# Microcontroller.net
KiCad netlist of a schematic drawn in Altium Designer
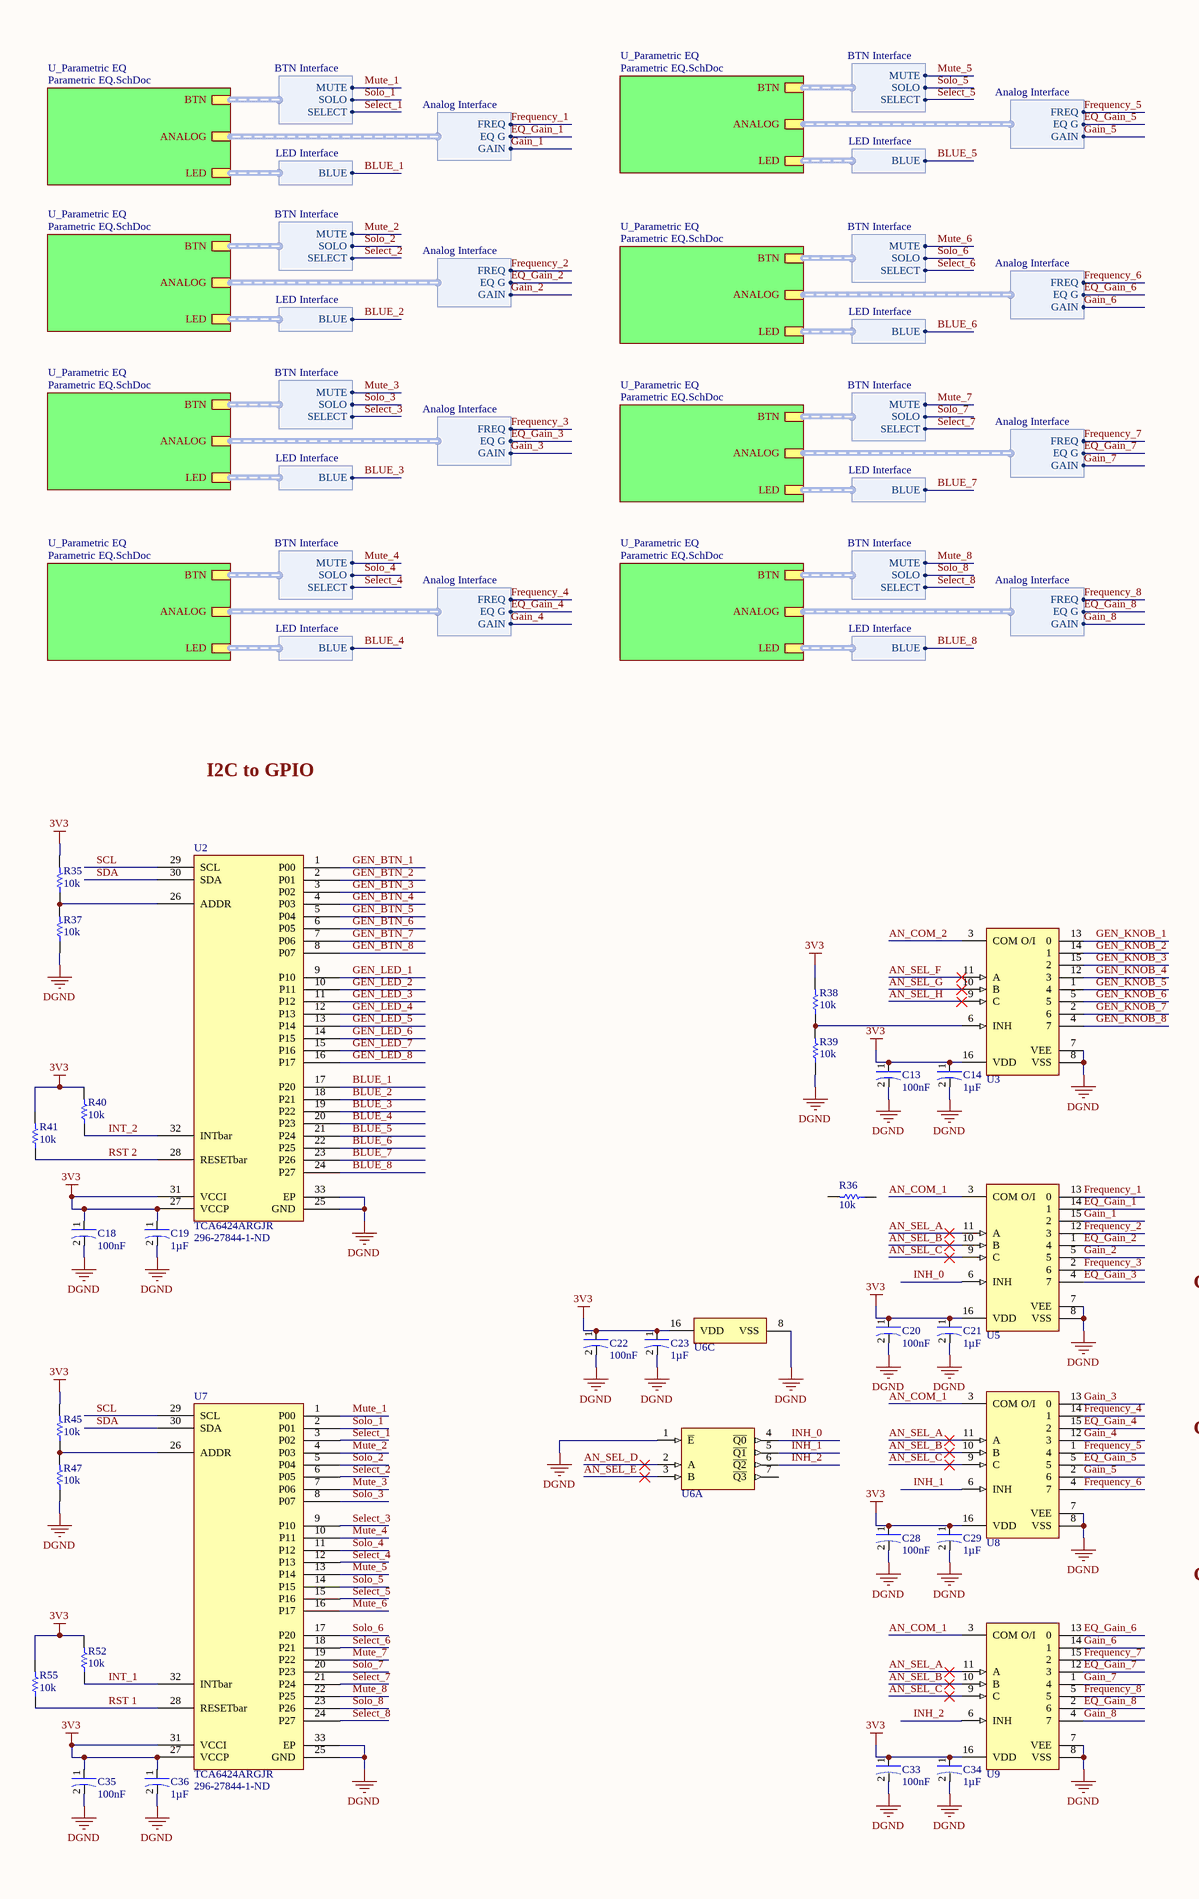
[diagram p0: Microcontroller.SchDoc, left]
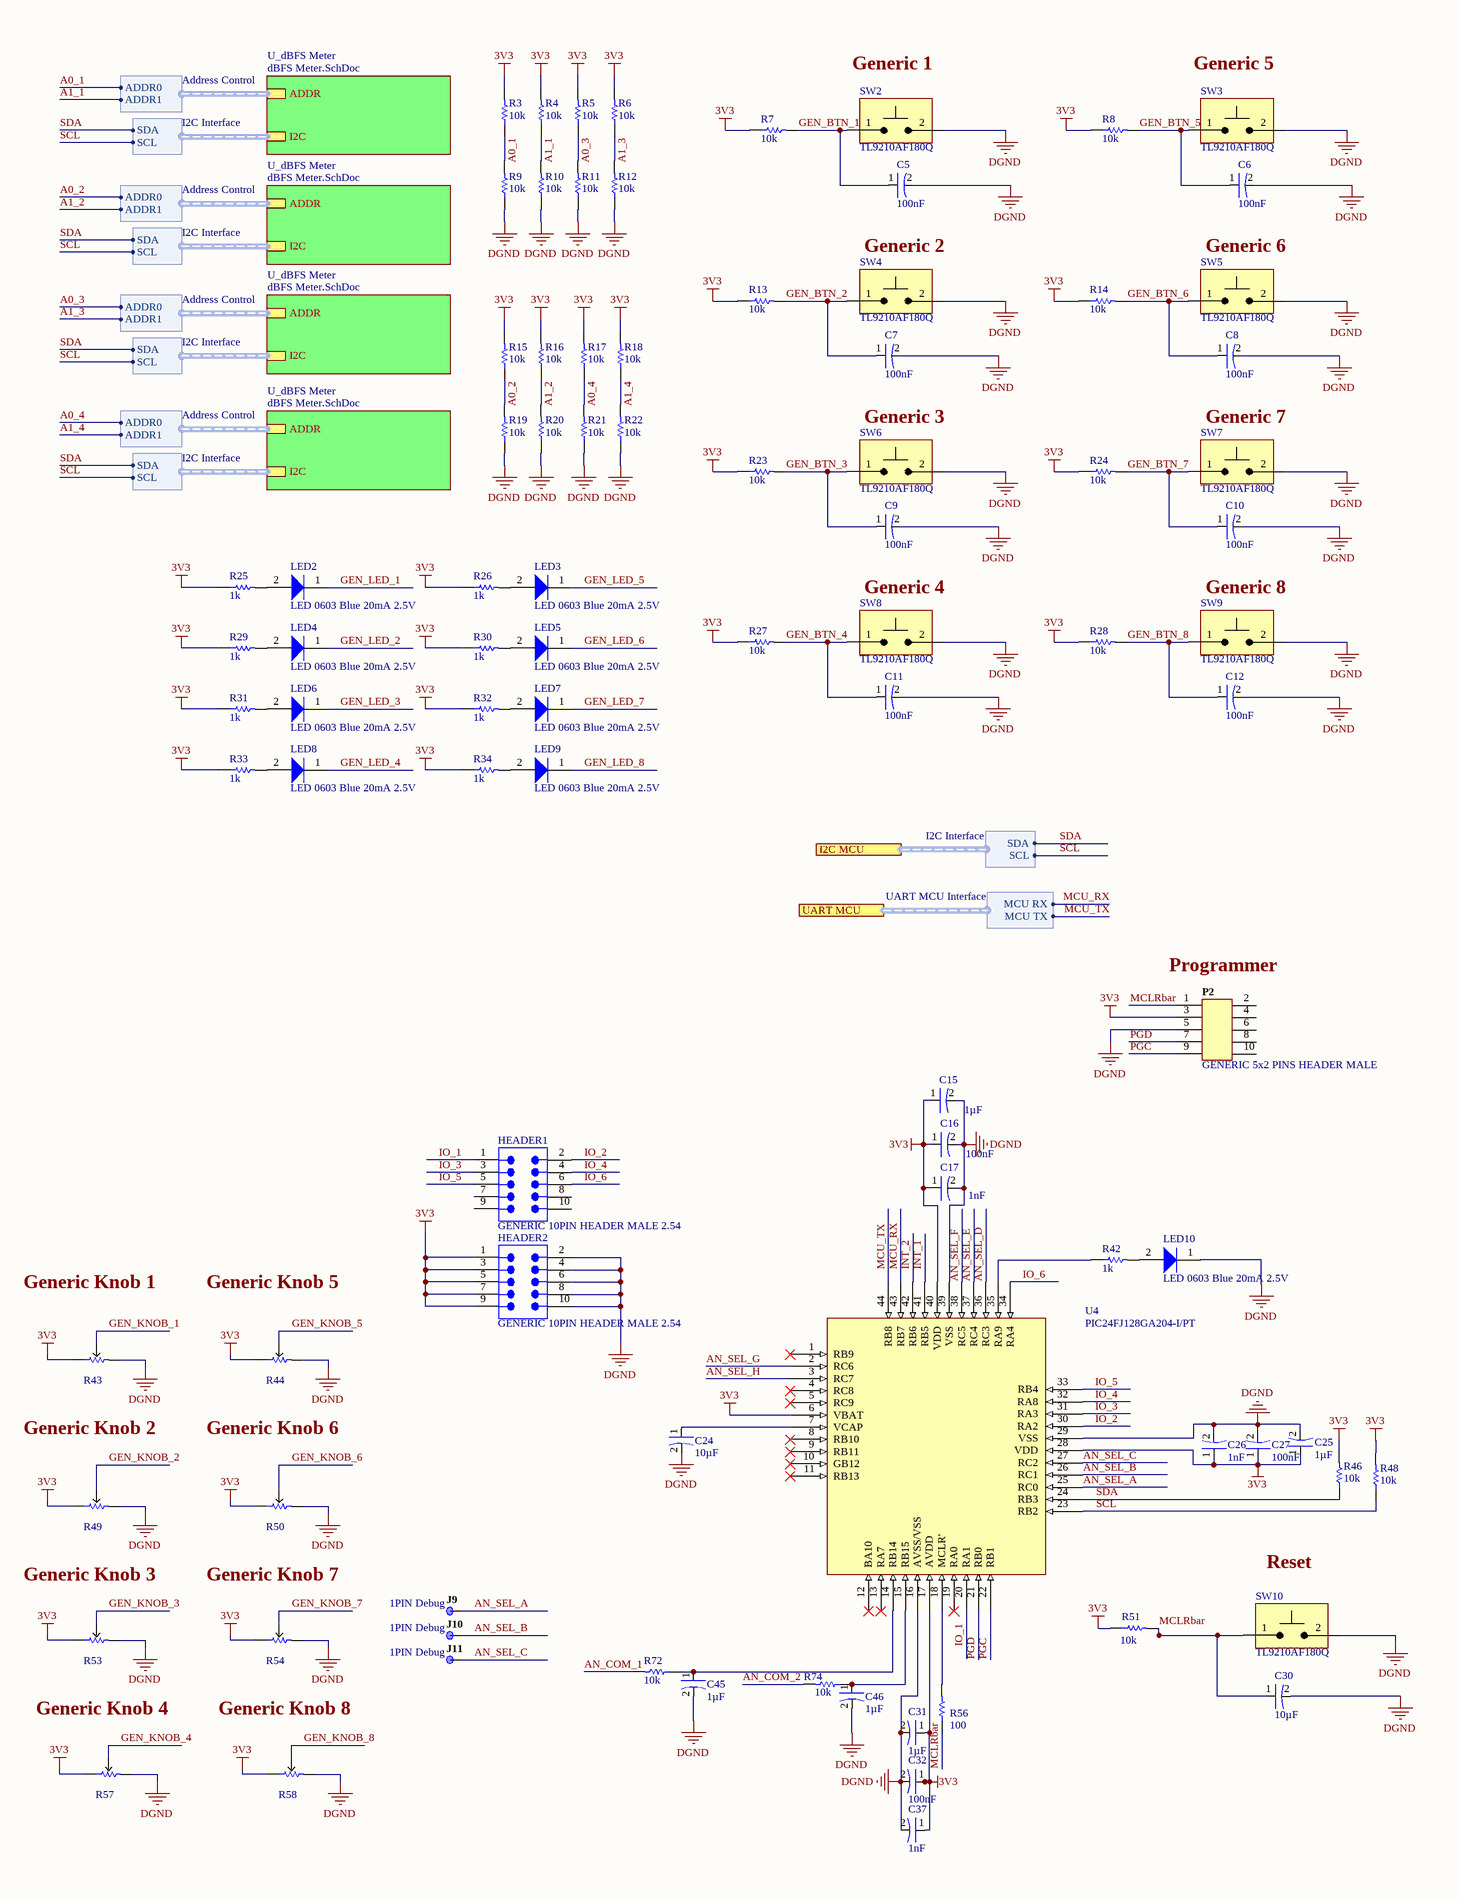
[diagram p1: Microcontroller.SchDoc, right]

(export (version "E")
  (design (tool "Eeschema 10.0.6"))
  (components
    (comp (ref "C5")
      (value "100nF")
      (footprint "0402-M")
      (description "CAP-0.1uF-CER-0402-16V-X5R-10%")
      (fields
        (field (name "MANUFACTURER") "Generic")
        (field (name "Comment") "CAP 0.1uF CER 0402 16V X5R 10%")
      )
      (libsource (lib "University of Malta - MEMENTO") (part "Symbol"))
    )
    (comp (ref "C6")
      (value "100nF")
      (footprint "0402-M")
      (description "CAP-0.1uF-CER-0402-16V-X5R-10%")
      (fields
        (field (name "MANUFACTURER") "Generic")
        (field (name "Comment") "CAP 0.1uF CER 0402 16V X5R 10%")
      )
      (libsource (lib "University of Malta - MEMENTO") (part "Symbol"))
    )
    (comp (ref "C7")
      (value "100nF")
      (footprint "0402-M")
      (description "CAP-0.1uF-CER-0402-16V-X5R-10%")
      (fields
        (field (name "MANUFACTURER") "Generic")
        (field (name "Comment") "CAP 0.1uF CER 0402 16V X5R 10%")
      )
      (libsource (lib "University of Malta - MEMENTO") (part "Symbol"))
    )
    (comp (ref "C8")
      (value "100nF")
      (footprint "0402-M")
      (description "CAP-0.1uF-CER-0402-16V-X5R-10%")
      (fields
        (field (name "MANUFACTURER") "Generic")
        (field (name "Comment") "CAP 0.1uF CER 0402 16V X5R 10%")
      )
      (libsource (lib "University of Malta - MEMENTO") (part "Symbol"))
    )
    (comp (ref "C9")
      (value "100nF")
      (footprint "0402-M")
      (description "CAP-0.1uF-CER-0402-16V-X5R-10%")
      (fields
        (field (name "MANUFACTURER") "Generic")
        (field (name "Comment") "CAP 0.1uF CER 0402 16V X5R 10%")
      )
      (libsource (lib "University of Malta - MEMENTO") (part "Symbol"))
    )
    (comp (ref "C10")
      (value "100nF")
      (footprint "0402-M")
      (description "CAP-0.1uF-CER-0402-16V-X5R-10%")
      (fields
        (field (name "MANUFACTURER") "Generic")
        (field (name "Comment") "CAP 0.1uF CER 0402 16V X5R 10%")
      )
      (libsource (lib "University of Malta - MEMENTO") (part "Symbol"))
    )
    (comp (ref "C11")
      (value "100nF")
      (footprint "0402-M")
      (description "CAP-0.1uF-CER-0402-16V-X5R-10%")
      (fields
        (field (name "MANUFACTURER") "Generic")
        (field (name "Comment") "CAP 0.1uF CER 0402 16V X5R 10%")
      )
      (libsource (lib "University of Malta - MEMENTO") (part "Symbol"))
    )
    (comp (ref "C12")
      (value "100nF")
      (footprint "0402-M")
      (description "CAP-0.1uF-CER-0402-16V-X5R-10%")
      (fields
        (field (name "MANUFACTURER") "Generic")
        (field (name "Comment") "CAP 0.1uF CER 0402 16V X5R 10%")
      )
      (libsource (lib "University of Malta - MEMENTO") (part "Symbol"))
    )
    (comp (ref "C13")
      (value "100nF")
      (footprint "0805-M")
      (description "CAP-0.1uF-CER-0805-50V- X7R-5%")
      (fields
        (field (name "MANUFACTURER") "Generic")
        (field (name "Comment") "CAP 0.1uF CER 0805 50V  X7R 5%")
      )
      (libsource (lib "University of Malta - MEMENTO") (part "Symbol"))
    )
    (comp (ref "C14")
      (value "1µF")
      (footprint "0805-M")
      (description "CAP 1uF CER 0805 25V C0G 10%")
      (fields (field (name "MANUFACTURER") "Generic"))
      (libsource (lib "University of Malta - MEMENTO") (part "Symbol"))
    )
    (comp (ref "C15")
      (value "1µF")
      (footprint "0805-M")
      (description "CAP 1uF CER 0805 25V C0G 10%")
      (fields (field (name "MANUFACTURER") "Generic"))
      (libsource (lib "University of Malta - MEMENTO") (part "Symbol"))
    )
    (comp (ref "C16")
      (value "100nF")
      (footprint "0805-M")
      (description "CAP-0.1uF-CER-0805-50V- X7R-5%")
      (fields
        (field (name "MANUFACTURER") "Generic")
        (field (name "Comment") "CAP 0.1uF CER 0805 50V  X7R 5%")
      )
      (libsource (lib "University of Malta - MEMENTO") (part "Symbol"))
    )
    (comp (ref "C17")
      (value "1nF")
      (footprint "0805-M")
      (description "CAP 1nF CER 0805 25V X7R 5%")
      (fields (field (name "MANUFACTURER") "Generic"))
      (libsource (lib "University of Malta - MEMENTO") (part "Symbol"))
    )
    (comp (ref "C18")
      (value "100nF")
      (footprint "0805-M")
      (description "CAP-0.1uF-CER-0805-50V- X7R-5%")
      (fields
        (field (name "MANUFACTURER") "Generic")
        (field (name "Comment") "CAP 0.1uF CER 0805 50V  X7R 5%")
      )
      (libsource (lib "University of Malta - MEMENTO") (part "Symbol"))
    )
    (comp (ref "C19")
      (value "1µF")
      (footprint "0805-M")
      (description "CAP 1uF CER 0805 25V C0G 10%")
      (fields (field (name "MANUFACTURER") "Generic"))
      (libsource (lib "University of Malta - MEMENTO") (part "Symbol"))
    )
    (comp (ref "C20")
      (value "100nF")
      (footprint "0805-M")
      (description "CAP-0.1uF-CER-0805-50V- X7R-5%")
      (fields
        (field (name "MANUFACTURER") "Generic")
        (field (name "Comment") "CAP 0.1uF CER 0805 50V  X7R 5%")
      )
      (libsource (lib "University of Malta - MEMENTO") (part "Symbol"))
    )
    (comp (ref "C21")
      (value "1µF")
      (footprint "0805-M")
      (description "CAP 1uF CER 0805 25V C0G 10%")
      (fields (field (name "MANUFACTURER") "Generic"))
      (libsource (lib "University of Malta - MEMENTO") (part "Symbol"))
    )
    (comp (ref "C22")
      (value "100nF")
      (footprint "0805-M")
      (description "CAP-0.1uF-CER-0805-50V- X7R-5%")
      (fields
        (field (name "MANUFACTURER") "Generic")
        (field (name "Comment") "CAP 0.1uF CER 0805 50V  X7R 5%")
      )
      (libsource (lib "University of Malta - MEMENTO") (part "Symbol"))
    )
    (comp (ref "C23")
      (value "1µF")
      (footprint "0805-M")
      (description "CAP 1uF CER 0805 25V C0G 10%")
      (fields (field (name "MANUFACTURER") "Generic"))
      (libsource (lib "University of Malta - MEMENTO") (part "Symbol"))
    )
    (comp (ref "C24")
      (value "10µF")
      (footprint "0805-M")
      (description "CAP-10uF-CER-0805-25V-X5R-10%")
      (fields
        (field (name "MANUFACTURER") "Generic")
        (field (name "Comment") "CAP 10uF CER 0805 25V X5R 10%")
      )
      (libsource (lib "University of Malta - MEMENTO") (part "Symbol"))
    )
    (comp (ref "C25")
      (value "1µF")
      (footprint "0805-M")
      (description "CAP 1uF CER 0805 25V C0G 10%")
      (fields (field (name "MANUFACTURER") "Generic"))
      (libsource (lib "University of Malta - MEMENTO") (part "Symbol"))
    )
    (comp (ref "C26")
      (value "1nF")
      (footprint "0805-M")
      (description "CAP 1nF CER 0805 25V X7R 5%")
      (fields (field (name "MANUFACTURER") "Generic"))
      (libsource (lib "University of Malta - MEMENTO") (part "Symbol"))
    )
    (comp (ref "C27")
      (value "100nF")
      (footprint "0805-M")
      (description "CAP-0.1uF-CER-0805-50V- X7R-5%")
      (fields
        (field (name "MANUFACTURER") "Generic")
        (field (name "Comment") "CAP 0.1uF CER 0805 50V  X7R 5%")
      )
      (libsource (lib "University of Malta - MEMENTO") (part "Symbol"))
    )
    (comp (ref "C28")
      (value "100nF")
      (footprint "0805-M")
      (description "CAP-0.1uF-CER-0805-50V- X7R-5%")
      (fields
        (field (name "MANUFACTURER") "Generic")
        (field (name "Comment") "CAP 0.1uF CER 0805 50V  X7R 5%")
      )
      (libsource (lib "University of Malta - MEMENTO") (part "Symbol"))
    )
    (comp (ref "C29")
      (value "1µF")
      (footprint "0805-M")
      (description "CAP 1uF CER 0805 25V C0G 10%")
      (fields (field (name "MANUFACTURER") "Generic"))
      (libsource (lib "University of Malta - MEMENTO") (part "Symbol"))
    )
    (comp (ref "C30")
      (value "10µF")
      (footprint "0402-M")
      (description "CAP-10uF-CER-0402-6.3V-X5R-20%")
      (fields
        (field (name "MANUFACTURER") "Generic")
        (field (name "Comment") "CAP 10uF CER 0402 6.3V X5R 20%")
      )
      (libsource (lib "University of Malta - MEMENTO") (part "Symbol"))
    )
    (comp (ref "C31")
      (value "1µF")
      (footprint "0805-M")
      (description "CAP 1uF CER 0805 25V C0G 10%")
      (fields (field (name "MANUFACTURER") "Generic"))
      (libsource (lib "University of Malta - MEMENTO") (part "Symbol"))
    )
    (comp (ref "C32")
      (value "100nF")
      (footprint "0805-M")
      (description "CAP-0.1uF-CER-0805-50V- X7R-5%")
      (fields
        (field (name "MANUFACTURER") "Generic")
        (field (name "Comment") "CAP 0.1uF CER 0805 50V  X7R 5%")
      )
      (libsource (lib "University of Malta - MEMENTO") (part "Symbol"))
    )
    (comp (ref "C33")
      (value "100nF")
      (footprint "0805-M")
      (description "CAP-0.1uF-CER-0805-50V- X7R-5%")
      (fields
        (field (name "MANUFACTURER") "Generic")
        (field (name "Comment") "CAP 0.1uF CER 0805 50V  X7R 5%")
      )
      (libsource (lib "University of Malta - MEMENTO") (part "Symbol"))
    )
    (comp (ref "C34")
      (value "1µF")
      (footprint "0805-M")
      (description "CAP 1uF CER 0805 25V C0G 10%")
      (fields (field (name "MANUFACTURER") "Generic"))
      (libsource (lib "University of Malta - MEMENTO") (part "Symbol"))
    )
    (comp (ref "C35")
      (value "100nF")
      (footprint "0805-M")
      (description "CAP-0.1uF-CER-0805-50V- X7R-5%")
      (fields
        (field (name "MANUFACTURER") "Generic")
        (field (name "Comment") "CAP 0.1uF CER 0805 50V  X7R 5%")
      )
      (libsource (lib "University of Malta - MEMENTO") (part "Symbol"))
    )
    (comp (ref "C36")
      (value "1µF")
      (footprint "0805-M")
      (description "CAP 1uF CER 0805 25V C0G 10%")
      (fields (field (name "MANUFACTURER") "Generic"))
      (libsource (lib "University of Malta - MEMENTO") (part "Symbol"))
    )
    (comp (ref "C37")
      (value "1nF")
      (footprint "0805-M")
      (description "CAP 1nF CER 0805 25V X7R 5%")
      (fields (field (name "MANUFACTURER") "Generic"))
      (libsource (lib "University of Malta - MEMENTO") (part "Symbol"))
    )
    (comp (ref "C45")
      (value "1µF")
      (footprint "0402-M")
      (description "CAP-1uF-CER-0402-6.3V-X5R-10%")
      (fields
        (field (name "MANUFACTURER") "Generic")
        (field (name "Comment") "CAP 1uF CER 0402 6.3V X5R 10%")
      )
      (libsource (lib "University of Malta - MEMENTO") (part "Symbol"))
    )
    (comp (ref "C46")
      (value "1µF")
      (footprint "0402-M")
      (description "CAP-1uF-CER-0402-6.3V-X5R-10%")
      (fields
        (field (name "MANUFACTURER") "Generic")
        (field (name "Comment") "CAP 1uF CER 0402 6.3V X5R 10%")
      )
      (libsource (lib "University of Malta - MEMENTO") (part "Symbol"))
    )
    (comp (ref "HEADER1")
      (value "GENERIC 10PIN HEADER MALE 2.54")
      (footprint "GENERIC 10Pin Header Male 2.54mm")
      (description "CONN MAL TH 10 0Deg HEADER 2.54mm")
      (fields
        (field (name "MANUFACTURER") "Generic")
        (field (name "DESIGN ITEM ID") "GENERIC 10PIN HEADER MALE 2.54")
      )
      (libsource (lib "University of Malta - MEMENTO") (part "GENERIC 10PIN HEADER MALE 2.54"))
    )
    (comp (ref "HEADER2")
      (value "GENERIC 10PIN HEADER MALE 2.54")
      (footprint "GENERIC 10Pin Header Male 2.54mm")
      (description "CONN MAL TH 10 0Deg HEADER 2.54mm")
      (fields
        (field (name "MANUFACTURER") "Generic")
        (field (name "DESIGN ITEM ID") "GENERIC 10PIN HEADER MALE 2.54")
      )
      (libsource (lib "University of Malta - MEMENTO") (part "GENERIC 10PIN HEADER MALE 2.54"))
    )
    (comp (ref "J9")
      (value "1PIN Debug")
      (footprint "1 Pin Debug Port 0.9mm")
      (description "CONN MAL TH 1 0Deg HEADER")
      (fields (field (name "DESIGN ITEM ID") "1PIN Debug"))
      (libsource (lib "University of Malta - MEMENTO") (part "1PIN Debug"))
    )
    (comp (ref "J10")
      (value "1PIN Debug")
      (footprint "1 Pin Debug Port 0.9mm")
      (description "CONN MAL TH 1 0Deg HEADER")
      (fields (field (name "DESIGN ITEM ID") "1PIN Debug"))
      (libsource (lib "University of Malta - MEMENTO") (part "1PIN Debug"))
    )
    (comp (ref "J11")
      (value "1PIN Debug")
      (footprint "1 Pin Debug Port 0.9mm")
      (description "CONN MAL TH 1 0Deg HEADER")
      (fields (field (name "DESIGN ITEM ID") "1PIN Debug"))
      (libsource (lib "University of Malta - MEMENTO") (part "1PIN Debug"))
    )
    (comp (ref "LED2")
      (value "LED 0603 Blue 20mA 2.5V")
      (footprint "VAOL-S6SB4")
      (description "LED-0603-Blue-20mA-2.5V-STOCK")
      (fields
        (field (name "DESIGN ITEM ID") "LED 0603 Blue 20mA 2.5V")
        (field (name "MANUFACTURER") "Generic")
      )
      (libsource (lib "") (part "Symbol_2"))
    )
    (comp (ref "LED3")
      (value "LED 0603 Blue 20mA 2.5V")
      (footprint "VAOL-S6SB4")
      (description "LED-0603-Blue-20mA-2.5V-STOCK")
      (fields
        (field (name "DESIGN ITEM ID") "LED 0603 Blue 20mA 2.5V")
        (field (name "MANUFACTURER") "Generic")
      )
      (libsource (lib "") (part "Symbol_2"))
    )
    (comp (ref "LED4")
      (value "LED 0603 Blue 20mA 2.5V")
      (footprint "VAOL-S6SB4")
      (description "LED-0603-Blue-20mA-2.5V-STOCK")
      (fields
        (field (name "DESIGN ITEM ID") "LED 0603 Blue 20mA 2.5V")
        (field (name "MANUFACTURER") "Generic")
      )
      (libsource (lib "") (part "Symbol_2"))
    )
    (comp (ref "LED5")
      (value "LED 0603 Blue 20mA 2.5V")
      (footprint "VAOL-S6SB4")
      (description "LED-0603-Blue-20mA-2.5V-STOCK")
      (fields
        (field (name "DESIGN ITEM ID") "LED 0603 Blue 20mA 2.5V")
        (field (name "MANUFACTURER") "Generic")
      )
      (libsource (lib "") (part "Symbol_2"))
    )
    (comp (ref "LED6")
      (value "LED 0603 Blue 20mA 2.5V")
      (footprint "VAOL-S6SB4")
      (description "LED-0603-Blue-20mA-2.5V-STOCK")
      (fields
        (field (name "DESIGN ITEM ID") "LED 0603 Blue 20mA 2.5V")
        (field (name "MANUFACTURER") "Generic")
      )
      (libsource (lib "") (part "Symbol_2"))
    )
    (comp (ref "LED7")
      (value "LED 0603 Blue 20mA 2.5V")
      (footprint "VAOL-S6SB4")
      (description "LED-0603-Blue-20mA-2.5V-STOCK")
      (fields
        (field (name "DESIGN ITEM ID") "LED 0603 Blue 20mA 2.5V")
        (field (name "MANUFACTURER") "Generic")
      )
      (libsource (lib "") (part "Symbol_2"))
    )
    (comp (ref "LED8")
      (value "LED 0603 Blue 20mA 2.5V")
      (footprint "VAOL-S6SB4")
      (description "LED-0603-Blue-20mA-2.5V-STOCK")
      (fields
        (field (name "DESIGN ITEM ID") "LED 0603 Blue 20mA 2.5V")
        (field (name "MANUFACTURER") "Generic")
      )
      (libsource (lib "") (part "Symbol_2"))
    )
    (comp (ref "LED9")
      (value "LED 0603 Blue 20mA 2.5V")
      (footprint "VAOL-S6SB4")
      (description "LED-0603-Blue-20mA-2.5V-STOCK")
      (fields
        (field (name "DESIGN ITEM ID") "LED 0603 Blue 20mA 2.5V")
        (field (name "MANUFACTURER") "Generic")
      )
      (libsource (lib "") (part "Symbol_2"))
    )
    (comp (ref "LED10")
      (value "LED 0603 Blue 20mA 2.5V")
      (footprint "VAOL-S6SB4")
      (description "LED-0603-Blue-20mA-2.5V-STOCK")
      (fields
        (field (name "DESIGN ITEM ID") "LED 0603 Blue 20mA 2.5V")
        (field (name "MANUFACTURER") "Generic")
      )
      (libsource (lib "") (part "Symbol_2"))
    )
    (comp (ref "P2")
      (value "GENERIC 5x2 PINS HEADER MALE")
      (footprint "GENERIC 5PIN 2ROW HEADER 0")
      (description "CONN MAL TH 5x2 0Deg HEADER")
      (fields
        (field (name "DESIGN ITEM ID") "GENERIC 5x2 PINS HEADER MALE")
        (field (name "MANUFACTURER") "Generic")
      )
      (libsource (lib "University of Malta - MEMENTO") (part "GENERIC 5x2 PINS HEADER MALE"))
    )
    (comp (ref "R3")
      (value "10k")
      (footprint "0402-M")
      (description "RES-10k-0402-63mW-5%")
      (fields (field (name "MANUFACTURER") "Generic") (field (name "Comment") "RES 10k 0402 63mW 5%"))
      (libsource (lib "") (part "Symbol_1"))
    )
    (comp (ref "R4")
      (value "10k")
      (footprint "0402-M")
      (description "RES-10k-0402-63mW-5%")
      (fields (field (name "MANUFACTURER") "Generic") (field (name "Comment") "RES 10k 0402 63mW 5%"))
      (libsource (lib "") (part "Symbol_1"))
    )
    (comp (ref "R5")
      (value "10k")
      (footprint "0402-M")
      (description "RES-10k-0402-63mW-5%")
      (fields (field (name "MANUFACTURER") "Generic") (field (name "Comment") "RES 10k 0402 63mW 5%"))
      (libsource (lib "") (part "Symbol_1"))
    )
    (comp (ref "R6")
      (value "10k")
      (footprint "0402-M")
      (description "RES-10k-0402-63mW-5%")
      (fields (field (name "MANUFACTURER") "Generic") (field (name "Comment") "RES 10k 0402 63mW 5%"))
      (libsource (lib "") (part "Symbol_1"))
    )
    (comp (ref "R7")
      (value "10k")
      (footprint "0402-M")
      (description "RES-10k-0402-63mW-5%")
      (fields (field (name "MANUFACTURER") "Generic") (field (name "Comment") "RES 10k 0402 63mW 5%"))
      (libsource (lib "") (part "Symbol_1"))
    )
    (comp (ref "R8")
      (value "10k")
      (footprint "0402-M")
      (description "RES-10k-0402-63mW-5%")
      (fields (field (name "MANUFACTURER") "Generic") (field (name "Comment") "RES 10k 0402 63mW 5%"))
      (libsource (lib "") (part "Symbol_1"))
    )
    (comp (ref "R9")
      (value "10k")
      (footprint "0402-M")
      (description "RES-10k-0402-63mW-5%")
      (fields (field (name "MANUFACTURER") "Generic") (field (name "Comment") "RES 10k 0402 63mW 5%"))
      (libsource (lib "") (part "Symbol_1"))
    )
    (comp (ref "R10")
      (value "10k")
      (footprint "0402-M")
      (description "RES-10k-0402-63mW-5%")
      (fields (field (name "MANUFACTURER") "Generic") (field (name "Comment") "RES 10k 0402 63mW 5%"))
      (libsource (lib "") (part "Symbol_1"))
    )
    (comp (ref "R11")
      (value "10k")
      (footprint "0402-M")
      (description "RES-10k-0402-63mW-5%")
      (fields (field (name "MANUFACTURER") "Generic") (field (name "Comment") "RES 10k 0402 63mW 5%"))
      (libsource (lib "") (part "Symbol_1"))
    )
    (comp (ref "R12")
      (value "10k")
      (footprint "0402-M")
      (description "RES-10k-0402-63mW-5%")
      (fields (field (name "MANUFACTURER") "Generic") (field (name "Comment") "RES 10k 0402 63mW 5%"))
      (libsource (lib "") (part "Symbol_1"))
    )
    (comp (ref "R13")
      (value "10k")
      (footprint "0402-M")
      (description "RES-10k-0402-63mW-5%")
      (fields (field (name "MANUFACTURER") "Generic") (field (name "Comment") "RES 10k 0402 63mW 5%"))
      (libsource (lib "") (part "Symbol_1"))
    )
    (comp (ref "R14")
      (value "10k")
      (footprint "0402-M")
      (description "RES-10k-0402-63mW-5%")
      (fields (field (name "MANUFACTURER") "Generic") (field (name "Comment") "RES 10k 0402 63mW 5%"))
      (libsource (lib "") (part "Symbol_1"))
    )
    (comp (ref "R15")
      (value "10k")
      (footprint "0402-M")
      (description "RES-10k-0402-63mW-5%")
      (fields (field (name "MANUFACTURER") "Generic") (field (name "Comment") "RES 10k 0402 63mW 5%"))
      (libsource (lib "") (part "Symbol_1"))
    )
    (comp (ref "R16")
      (value "10k")
      (footprint "0402-M")
      (description "RES-10k-0402-63mW-5%")
      (fields (field (name "MANUFACTURER") "Generic") (field (name "Comment") "RES 10k 0402 63mW 5%"))
      (libsource (lib "") (part "Symbol_1"))
    )
    (comp (ref "R17")
      (value "10k")
      (footprint "0402-M")
      (description "RES-10k-0402-63mW-5%")
      (fields (field (name "MANUFACTURER") "Generic") (field (name "Comment") "RES 10k 0402 63mW 5%"))
      (libsource (lib "") (part "Symbol_1"))
    )
    (comp (ref "R18")
      (value "10k")
      (footprint "0402-M")
      (description "RES-10k-0402-63mW-5%")
      (fields (field (name "MANUFACTURER") "Generic") (field (name "Comment") "RES 10k 0402 63mW 5%"))
      (libsource (lib "") (part "Symbol_1"))
    )
    (comp (ref "R19")
      (value "10k")
      (footprint "0402-M")
      (description "RES-10k-0402-63mW-5%")
      (fields (field (name "MANUFACTURER") "Generic") (field (name "Comment") "RES 10k 0402 63mW 5%"))
      (libsource (lib "") (part "Symbol_1"))
    )
    (comp (ref "R20")
      (value "10k")
      (footprint "0402-M")
      (description "RES-10k-0402-63mW-5%")
      (fields (field (name "MANUFACTURER") "Generic") (field (name "Comment") "RES 10k 0402 63mW 5%"))
      (libsource (lib "") (part "Symbol_1"))
    )
    (comp (ref "R21")
      (value "10k")
      (footprint "0402-M")
      (description "RES-10k-0402-63mW-5%")
      (fields (field (name "MANUFACTURER") "Generic") (field (name "Comment") "RES 10k 0402 63mW 5%"))
      (libsource (lib "") (part "Symbol_1"))
    )
    (comp (ref "R22")
      (value "10k")
      (footprint "0402-M")
      (description "RES-10k-0402-63mW-5%")
      (fields (field (name "MANUFACTURER") "Generic") (field (name "Comment") "RES 10k 0402 63mW 5%"))
      (libsource (lib "") (part "Symbol_1"))
    )
    (comp (ref "R23")
      (value "10k")
      (footprint "0402-M")
      (description "RES-10k-0402-63mW-5%")
      (fields (field (name "MANUFACTURER") "Generic") (field (name "Comment") "RES 10k 0402 63mW 5%"))
      (libsource (lib "") (part "Symbol_1"))
    )
    (comp (ref "R24")
      (value "10k")
      (footprint "0402-M")
      (description "RES-10k-0402-63mW-5%")
      (fields (field (name "MANUFACTURER") "Generic") (field (name "Comment") "RES 10k 0402 63mW 5%"))
      (libsource (lib "") (part "Symbol_1"))
    )
    (comp (ref "R25")
      (value "1k")
      (footprint "0402-M")
      (description "RES-1k-0402-63mW-1%")
      (fields (field (name "MANUFACTURER") "Generic") (field (name "Comment") "RES 1k 0402 63mW 1%"))
      (libsource (lib "") (part "Symbol_1"))
    )
    (comp (ref "R26")
      (value "1k")
      (footprint "0402-M")
      (description "RES-1k-0402-63mW-1%")
      (fields (field (name "MANUFACTURER") "Generic") (field (name "Comment") "RES 1k 0402 63mW 1%"))
      (libsource (lib "") (part "Symbol_1"))
    )
    (comp (ref "R27")
      (value "10k")
      (footprint "0402-M")
      (description "RES-10k-0402-63mW-5%")
      (fields (field (name "MANUFACTURER") "Generic") (field (name "Comment") "RES 10k 0402 63mW 5%"))
      (libsource (lib "") (part "Symbol_1"))
    )
    (comp (ref "R28")
      (value "10k")
      (footprint "0402-M")
      (description "RES-10k-0402-63mW-5%")
      (fields (field (name "MANUFACTURER") "Generic") (field (name "Comment") "RES 10k 0402 63mW 5%"))
      (libsource (lib "") (part "Symbol_1"))
    )
    (comp (ref "R29")
      (value "1k")
      (footprint "0402-M")
      (description "RES-1k-0402-63mW-1%")
      (fields (field (name "MANUFACTURER") "Generic") (field (name "Comment") "RES 1k 0402 63mW 1%"))
      (libsource (lib "") (part "Symbol_1"))
    )
    (comp (ref "R30")
      (value "1k")
      (footprint "0402-M")
      (description "RES-1k-0402-63mW-1%")
      (fields (field (name "MANUFACTURER") "Generic") (field (name "Comment") "RES 1k 0402 63mW 1%"))
      (libsource (lib "") (part "Symbol_1"))
    )
    (comp (ref "R31")
      (value "1k")
      (footprint "0402-M")
      (description "RES-1k-0402-63mW-1%")
      (fields (field (name "MANUFACTURER") "Generic") (field (name "Comment") "RES 1k 0402 63mW 1%"))
      (libsource (lib "") (part "Symbol_1"))
    )
    (comp (ref "R32")
      (value "1k")
      (footprint "0402-M")
      (description "RES-1k-0402-63mW-1%")
      (fields (field (name "MANUFACTURER") "Generic") (field (name "Comment") "RES 1k 0402 63mW 1%"))
      (libsource (lib "") (part "Symbol_1"))
    )
    (comp (ref "R33")
      (value "1k")
      (footprint "0402-M")
      (description "RES-1k-0402-63mW-1%")
      (fields (field (name "MANUFACTURER") "Generic") (field (name "Comment") "RES 1k 0402 63mW 1%"))
      (libsource (lib "") (part "Symbol_1"))
    )
    (comp (ref "R34")
      (value "1k")
      (footprint "0402-M")
      (description "RES-1k-0402-63mW-1%")
      (fields (field (name "MANUFACTURER") "Generic") (field (name "Comment") "RES 1k 0402 63mW 1%"))
      (libsource (lib "") (part "Symbol_1"))
    )
    (comp (ref "R35")
      (value "10k")
      (footprint "0805-M")
      (description "RES-10k-0805-125mW-1%")
      (fields (field (name "MANUFACTURER") "Generic") (field (name "Comment") "RES 10k 0805 125mW 1%"))
      (libsource (lib "") (part "Symbol_1"))
    )
    (comp (ref "R36")
      (value "10k")
      (footprint "0402-M")
      (description "RES-10k-0402-63mW-5%")
      (fields (field (name "MANUFACTURER") "Generic") (field (name "Comment") "RES 10k 0402 63mW 5%"))
      (libsource (lib "") (part "Symbol_1"))
    )
    (comp (ref "R37")
      (value "10k")
      (footprint "0805-M")
      (description "RES-10k-0805-125mW-1%")
      (fields (field (name "MANUFACTURER") "Generic") (field (name "Comment") "RES 10k 0805 125mW 1%"))
      (libsource (lib "") (part "Symbol_1"))
    )
    (comp (ref "R38")
      (value "10k")
      (footprint "0805-M")
      (description "RES-10k-0805-125mW-1%")
      (fields (field (name "MANUFACTURER") "Generic") (field (name "Comment") "RES 10k 0805 125mW 1%"))
      (libsource (lib "") (part "Symbol_1"))
    )
    (comp (ref "R39")
      (value "10k")
      (footprint "0805-M")
      (description "RES-10k-0805-125mW-1%")
      (fields (field (name "MANUFACTURER") "Generic") (field (name "Comment") "RES 10k 0805 125mW 1%"))
      (libsource (lib "") (part "Symbol_1"))
    )
    (comp (ref "R40")
      (value "10k")
      (footprint "0805-M")
      (description "RES-10k-0805-125mW-1%")
      (fields (field (name "MANUFACTURER") "Generic") (field (name "Comment") "RES 10k 0805 125mW 1%"))
      (libsource (lib "") (part "Symbol_1"))
    )
    (comp (ref "R41")
      (value "10k")
      (footprint "0805-M")
      (description "RES-10k-0805-125mW-1%")
      (fields (field (name "MANUFACTURER") "Generic") (field (name "Comment") "RES 10k 0805 125mW 1%"))
      (libsource (lib "") (part "Symbol_1"))
    )
    (comp (ref "R42")
      (value "1k")
      (footprint "0402-M")
      (description "RES-1k-0402-63mW-1%")
      (fields (field (name "MANUFACTURER") "Generic") (field (name "Comment") "RES 1k 0402 63mW 1%"))
      (libsource (lib "") (part "Symbol_1"))
    )
    (comp (ref "R43")
      (value "P120PK-Y25BR10K")
      (footprint "P120PK-Y25BR10K-Footprint-1")
      (description "Potentiometers 12mm 10K ohm")
      (fields (field (name "TOLERANCE") "20%"))
      (libsource (lib "University of Malta - MEMENTO") (part "P120PK-Y25BR10K"))
    )
    (comp (ref "R44")
      (value "P120PK-Y25BR10K")
      (footprint "P120PK-Y25BR10K-Footprint-1")
      (description "Potentiometers 12mm 10K ohm")
      (fields (field (name "TOLERANCE") "20%"))
      (libsource (lib "University of Malta - MEMENTO") (part "P120PK-Y25BR10K"))
    )
    (comp (ref "R45")
      (value "10k")
      (footprint "0805-M")
      (description "RES-10k-0805-125mW-1%")
      (fields (field (name "MANUFACTURER") "Generic") (field (name "Comment") "RES 10k 0805 125mW 1%"))
      (libsource (lib "") (part "Symbol_1"))
    )
    (comp (ref "R46")
      (value "10k")
      (footprint "0805-M")
      (description "RES-10k-0805-125mW-1%")
      (fields (field (name "MANUFACTURER") "Generic") (field (name "Comment") "RES 10k 0805 125mW 1%"))
      (libsource (lib "") (part "Symbol_1"))
    )
    (comp (ref "R47")
      (value "10k")
      (footprint "0805-M")
      (description "RES-10k-0805-125mW-1%")
      (fields (field (name "MANUFACTURER") "Generic") (field (name "Comment") "RES 10k 0805 125mW 1%"))
      (libsource (lib "") (part "Symbol_1"))
    )
    (comp (ref "R48")
      (value "10k")
      (footprint "0805-M")
      (description "RES-10k-0805-125mW-1%")
      (fields (field (name "MANUFACTURER") "Generic") (field (name "Comment") "RES 10k 0805 125mW 1%"))
      (libsource (lib "") (part "Symbol_1"))
    )
    (comp (ref "R49")
      (value "P120PK-Y25BR10K")
      (footprint "P120PK-Y25BR10K-Footprint-1")
      (description "Potentiometers 12mm 10K ohm")
      (fields (field (name "TOLERANCE") "20%"))
      (libsource (lib "University of Malta - MEMENTO") (part "P120PK-Y25BR10K"))
    )
    (comp (ref "R50")
      (value "P120PK-Y25BR10K")
      (footprint "P120PK-Y25BR10K-Footprint-1")
      (description "Potentiometers 12mm 10K ohm")
      (fields (field (name "TOLERANCE") "20%"))
      (libsource (lib "University of Malta - MEMENTO") (part "P120PK-Y25BR10K"))
    )
    (comp (ref "R51")
      (value "10k")
      (footprint "0402-M")
      (description "RES-10k-0402-63mW-5%")
      (fields (field (name "MANUFACTURER") "Generic") (field (name "Comment") "RES 10k 0402 63mW 5%"))
      (libsource (lib "") (part "Symbol_1"))
    )
    (comp (ref "R52")
      (value "10k")
      (footprint "0805-M")
      (description "RES-10k-0805-125mW-1%")
      (fields (field (name "MANUFACTURER") "Generic") (field (name "Comment") "RES 10k 0805 125mW 1%"))
      (libsource (lib "") (part "Symbol_1"))
    )
    (comp (ref "R53")
      (value "P120PK-Y25BR10K")
      (footprint "P120PK-Y25BR10K-Footprint-1")
      (description "Potentiometers 12mm 10K ohm")
      (fields (field (name "TOLERANCE") "20%"))
      (libsource (lib "University of Malta - MEMENTO") (part "P120PK-Y25BR10K"))
    )
    (comp (ref "R54")
      (value "P120PK-Y25BR10K")
      (footprint "P120PK-Y25BR10K-Footprint-1")
      (description "Potentiometers 12mm 10K ohm")
      (fields (field (name "TOLERANCE") "20%"))
      (libsource (lib "University of Malta - MEMENTO") (part "P120PK-Y25BR10K"))
    )
    (comp (ref "R55")
      (value "10k")
      (footprint "0805-M")
      (description "RES-10k-0805-125mW-1%")
      (fields (field (name "MANUFACTURER") "Generic") (field (name "Comment") "RES 10k 0805 125mW 1%"))
      (libsource (lib "") (part "Symbol_1"))
    )
    (comp (ref "R56")
      (value "100")
      (footprint "0805-L")
      (description "RES-100-0805-125mW-1%")
      (fields (field (name "MANUFACTURER") "Generic") (field (name "Comment") "RES 100 0805 125mW 1%"))
      (libsource (lib "") (part "Symbol_1"))
    )
    (comp (ref "R57")
      (value "P120PK-Y25BR10K")
      (footprint "P120PK-Y25BR10K-Footprint-1")
      (description "Potentiometers 12mm 10K ohm")
      (fields (field (name "TOLERANCE") "20%"))
      (libsource (lib "University of Malta - MEMENTO") (part "P120PK-Y25BR10K"))
    )
    (comp (ref "R58")
      (value "P120PK-Y25BR10K")
      (footprint "P120PK-Y25BR10K-Footprint-1")
      (description "Potentiometers 12mm 10K ohm")
      (fields (field (name "TOLERANCE") "20%"))
      (libsource (lib "University of Malta - MEMENTO") (part "P120PK-Y25BR10K"))
    )
    (comp (ref "R72")
      (value "10k")
      (footprint "0402-M")
      (description "RES-10k-0402-63mW-5%")
      (fields (field (name "MANUFACTURER") "Generic") (field (name "Comment") "RES 10k 0402 63mW 5%"))
      (libsource (lib "") (part "Symbol_1"))
    )
    (comp (ref "R74")
      (value "10k")
      (footprint "0402-M")
      (description "RES-10k-0402-63mW-5%")
      (fields (field (name "MANUFACTURER") "Generic") (field (name "Comment") "RES 10k 0402 63mW 5%"))
      (libsource (lib "") (part "Symbol_1"))
    )
    (comp (ref "SW2")
      (value "TL9210AF180Q")
      (footprint "TL9210")
      (description "SWITCH MOM SMD SPST 50MA 12V Soft Tact")
      (fields (field (name "MANUFACTURER") "E-Switch") (field (name "DESIGN ITEM ID") "TL9210AF180Q"))
      (libsource (lib "") (part "Symbol_3"))
    )
    (comp (ref "SW3")
      (value "TL9210AF180Q")
      (footprint "TL9210")
      (description "SWITCH MOM SMD SPST 50MA 12V Soft Tact")
      (fields (field (name "MANUFACTURER") "E-Switch") (field (name "DESIGN ITEM ID") "TL9210AF180Q"))
      (libsource (lib "") (part "Symbol_3"))
    )
    (comp (ref "SW4")
      (value "TL9210AF180Q")
      (footprint "TL9210")
      (description "SWITCH MOM SMD SPST 50MA 12V Soft Tact")
      (fields (field (name "MANUFACTURER") "E-Switch") (field (name "DESIGN ITEM ID") "TL9210AF180Q"))
      (libsource (lib "") (part "Symbol_3"))
    )
    (comp (ref "SW5")
      (value "TL9210AF180Q")
      (footprint "TL9210")
      (description "SWITCH MOM SMD SPST 50MA 12V Soft Tact")
      (fields (field (name "MANUFACTURER") "E-Switch") (field (name "DESIGN ITEM ID") "TL9210AF180Q"))
      (libsource (lib "") (part "Symbol_3"))
    )
    (comp (ref "SW6")
      (value "TL9210AF180Q")
      (footprint "TL9210")
      (description "SWITCH MOM SMD SPST 50MA 12V Soft Tact")
      (fields (field (name "MANUFACTURER") "E-Switch") (field (name "DESIGN ITEM ID") "TL9210AF180Q"))
      (libsource (lib "") (part "Symbol_3"))
    )
    (comp (ref "SW7")
      (value "TL9210AF180Q")
      (footprint "TL9210")
      (description "SWITCH MOM SMD SPST 50MA 12V Soft Tact")
      (fields (field (name "MANUFACTURER") "E-Switch") (field (name "DESIGN ITEM ID") "TL9210AF180Q"))
      (libsource (lib "") (part "Symbol_3"))
    )
    (comp (ref "SW8")
      (value "TL9210AF180Q")
      (footprint "TL9210")
      (description "SWITCH MOM SMD SPST 50MA 12V Soft Tact")
      (fields (field (name "MANUFACTURER") "E-Switch") (field (name "DESIGN ITEM ID") "TL9210AF180Q"))
      (libsource (lib "") (part "Symbol_3"))
    )
    (comp (ref "SW9")
      (value "TL9210AF180Q")
      (footprint "TL9210")
      (description "SWITCH MOM SMD SPST 50MA 12V Soft Tact")
      (fields (field (name "MANUFACTURER") "E-Switch") (field (name "DESIGN ITEM ID") "TL9210AF180Q"))
      (libsource (lib "") (part "Symbol_3"))
    )
    (comp (ref "SW10")
      (value "TL9210AF180Q")
      (footprint "TL9210")
      (description "SWITCH MOM SMD SPST 50MA 12V Soft Tact")
      (fields (field (name "MANUFACTURER") "E-Switch") (field (name "DESIGN ITEM ID") "TL9210AF180Q"))
      (libsource (lib "") (part "Symbol_3"))
    )
    (comp (ref "U2")
      (value "TCA6424ARGJR")
      (footprint "TCA6424ARGJR")
      (fields (field (name "SUPPLIER PART NUMBER 1") "296-27844-1-ND"))
      (libsource (lib "texas") (part "TCA6424ARGJR"))
    )
    (comp (ref "U3")
      (value "CD4051BM")
      (footprint "D0016A_M")
      (description "Analog Multiplexer Single 8:1 16-Pin SOIC Tube")
      (libsource (lib "University of Malta - MEMENTO") (part "TI-CD4051B-16"))
    )
    (comp (ref "U4")
      (value "PIC24FJ128GA204-I/PT")
      (footprint "CQFP80P1415X1415X120-44N")
      (description "IC MCU 16BIT 128KB FLASH 44TQFP")
      (fields (field (name "MANUFACTURER") "Microchip"))
      (libsource (lib "University of Malta - MEMENTO") (part "PIC24FJ128GA204-I_PT"))
    )
    (comp (ref "U5")
      (value "CD4051BM")
      (footprint "D0016A_M")
      (description "Analog Multiplexer Single 8:1 16-Pin SOIC Tube")
      (libsource (lib "University of Malta - MEMENTO") (part "TI-CD4051B-16"))
    )
    (comp (ref "U6")
      (value "CD4556BM96")
      (footprint "D0016A_M")
      (description "Decoder/Demultiplexer Dual 2-to-4 16-Pin SOIC T/R")
      (libsource (lib "University of Malta - MEMENTO") (part "TI-CD4556B-16"))
    )
    (comp (ref "U7")
      (value "TCA6424ARGJR")
      (footprint "TCA6424ARGJR")
      (fields (field (name "SUPPLIER PART NUMBER 1") "296-27844-1-ND"))
      (libsource (lib "texas") (part "TCA6424ARGJR"))
    )
    (comp (ref "U8")
      (value "CD4051BM")
      (footprint "D0016A_M")
      (description "Analog Multiplexer Single 8:1 16-Pin SOIC Tube")
      (libsource (lib "University of Malta - MEMENTO") (part "TI-CD4051B-16"))
    )
    (comp (ref "U9")
      (value "CD4051BM")
      (footprint "D0016A_M")
      (description "Analog Multiplexer Single 8:1 16-Pin SOIC Tube")
      (libsource (lib "University of Malta - MEMENTO") (part "TI-CD4051B-16"))
    )
  )
  (nets
    (net (code "10") (name "/A0_1") (class "Default")
      (node (ref "R3") (pin "1") (pinfunction "1_1") (pintype "passive"))
      (node (ref "R9") (pin "2") (pinfunction "2_2") (pintype "passive"))
    )
    (net (code "11") (name "/A0_2") (class "Default")
      (node (ref "R15") (pin "1") (pinfunction "1_1") (pintype "passive"))
      (node (ref "R19") (pin "2") (pinfunction "2_2") (pintype "passive"))
    )
    (net (code "12") (name "/A0_3") (class "Default")
      (node (ref "R11") (pin "2") (pinfunction "2_2") (pintype "passive"))
      (node (ref "R5") (pin "1") (pinfunction "1_1") (pintype "passive"))
    )
    (net (code "13") (name "/A0_4") (class "Default")
      (node (ref "R17") (pin "1") (pinfunction "1_1") (pintype "passive"))
      (node (ref "R21") (pin "2") (pinfunction "2_2") (pintype "passive"))
    )
    (net (code "14") (name "/A1_1") (class "Default")
      (node (ref "R10") (pin "2") (pinfunction "2_2") (pintype "passive"))
      (node (ref "R4") (pin "1") (pinfunction "1_1") (pintype "passive"))
    )
    (net (code "15") (name "/A1_2") (class "Default")
      (node (ref "R16") (pin "1") (pinfunction "1_1") (pintype "passive"))
      (node (ref "R20") (pin "2") (pinfunction "2_2") (pintype "passive"))
    )
    (net (code "16") (name "/A1_3") (class "Default")
      (node (ref "R12") (pin "2") (pinfunction "2_2") (pintype "passive"))
      (node (ref "R6") (pin "1") (pinfunction "1_1") (pintype "passive"))
    )
    (net (code "17") (name "/A1_4") (class "Default")
      (node (ref "R18") (pin "1") (pinfunction "1_1") (pintype "passive"))
      (node (ref "R22") (pin "2") (pinfunction "2_2") (pintype "passive"))
    )
    (net (code "18") (name "/AN_COM_1") (class "Default")
      (node (ref "R72") (pin "2") (pinfunction "2_2") (pintype "passive"))
      (node (ref "U5") (pin "3") (pinfunction "COM_O/I_3") (pintype "passive"))
      (node (ref "U8") (pin "3") (pinfunction "COM_O/I_3") (pintype "passive"))
      (node (ref "U9") (pin "3") (pinfunction "COM_O/I_3") (pintype "passive"))
    )
    (net (code "19") (name "/AN_COM_2") (class "Default")
      (node (ref "R74") (pin "2") (pinfunction "2_2") (pintype "passive"))
      (node (ref "U3") (pin "3") (pinfunction "COM_O/I_3") (pintype "passive"))
    )
    (net (code "20") (name "/AN_SEL_A") (class "Default")
      (node (ref "J9") (pin "1") (pinfunction "1_1") (pintype "passive"))
      (node (ref "U4") (pin "25") (pinfunction "RC0_25") (pintype "input"))
      (node (ref "U5") (pin "11") (pinfunction "A_11") (pintype "input"))
      (node (ref "U8") (pin "11") (pinfunction "A_11") (pintype "input"))
      (node (ref "U9") (pin "11") (pinfunction "A_11") (pintype "input"))
    )
    (net (code "21") (name "/AN_SEL_B") (class "Default")
      (node (ref "J10") (pin "1") (pinfunction "1_1") (pintype "passive"))
      (node (ref "U4") (pin "26") (pinfunction "RC1_26") (pintype "input"))
      (node (ref "U5") (pin "10") (pinfunction "B_10") (pintype "input"))
      (node (ref "U8") (pin "10") (pinfunction "B_10") (pintype "input"))
      (node (ref "U9") (pin "10") (pinfunction "B_10") (pintype "input"))
    )
    (net (code "22") (name "/AN_SEL_C") (class "Default")
      (node (ref "J11") (pin "1") (pinfunction "1_1") (pintype "passive"))
      (node (ref "U4") (pin "27") (pinfunction "RC2_27") (pintype "input"))
      (node (ref "U5") (pin "9") (pinfunction "C_9") (pintype "input"))
      (node (ref "U8") (pin "9") (pinfunction "C_9") (pintype "input"))
      (node (ref "U9") (pin "9") (pinfunction "C_9") (pintype "input"))
    )
    (net (code "23") (name "/AN_SEL_D") (class "Default")
      (node (ref "U4") (pin "36") (pinfunction "RC3_36") (pintype "input"))
      (node (ref "U6") (pin "2") (pinfunction "A_2") (pintype "input"))
    )
    (net (code "24") (name "/AN_SEL_E") (class "Default")
      (node (ref "U4") (pin "37") (pinfunction "RC4_37") (pintype "input"))
      (node (ref "U6") (pin "3") (pinfunction "B_3") (pintype "input"))
    )
    (net (code "25") (name "/AN_SEL_F") (class "Default")
      (node (ref "U3") (pin "11") (pinfunction "A_11") (pintype "input"))
      (node (ref "U4") (pin "38") (pinfunction "RC5_38") (pintype "input"))
    )
    (net (code "26") (name "/AN_SEL_G") (class "Default")
      (node (ref "U3") (pin "10") (pinfunction "B_10") (pintype "input"))
      (node (ref "U4") (pin "2") (pinfunction "RC6_2") (pintype "input"))
    )
    (net (code "27") (name "/AN_SEL_H") (class "Default")
      (node (ref "U3") (pin "9") (pinfunction "C_9") (pintype "input"))
      (node (ref "U4") (pin "3") (pinfunction "RC7_3") (pintype "input"))
    )
    (net (code "28") (name "/BLUE_1") (class "Default")
      (node (ref "U2") (pin "17") (pinfunction "P20_17") (pintype "passive"))
    )
    (net (code "29") (name "/BLUE_2") (class "Default")
      (node (ref "U2") (pin "18") (pinfunction "P21_18") (pintype "passive"))
    )
    (net (code "30") (name "/BLUE_3") (class "Default")
      (node (ref "U2") (pin "19") (pinfunction "P22_19") (pintype "passive"))
    )
    (net (code "31") (name "/BLUE_4") (class "Default")
      (node (ref "U2") (pin "20") (pinfunction "P23_20") (pintype "passive"))
    )
    (net (code "32") (name "/BLUE_5") (class "Default")
      (node (ref "U2") (pin "21") (pinfunction "P24_21") (pintype "passive"))
    )
    (net (code "33") (name "/BLUE_6") (class "Default")
      (node (ref "U2") (pin "22") (pinfunction "P25_22") (pintype "passive"))
    )
    (net (code "34") (name "/BLUE_7") (class "Default")
      (node (ref "U2") (pin "23") (pinfunction "P26_23") (pintype "passive"))
    )
    (net (code "35") (name "/BLUE_8") (class "Default")
      (node (ref "U2") (pin "24") (pinfunction "P27_24") (pintype "passive"))
    )
    (net (code "36") (name "/EQ_Gain_1") (class "Default")
      (node (ref "U5") (pin "14") (pinfunction "1_14") (pintype "passive"))
    )
    (net (code "37") (name "/EQ_Gain_2") (class "Default")
      (node (ref "U5") (pin "1") (pinfunction "4_1") (pintype "passive"))
    )
    (net (code "38") (name "/EQ_Gain_3") (class "Default")
      (node (ref "U5") (pin "4") (pinfunction "7_4") (pintype "passive"))
    )
    (net (code "39") (name "/EQ_Gain_4") (class "Default")
      (node (ref "U8") (pin "15") (pinfunction "2_15") (pintype "passive"))
    )
    (net (code "40") (name "/EQ_Gain_5") (class "Default")
      (node (ref "U8") (pin "5") (pinfunction "5_5") (pintype "passive"))
    )
    (net (code "41") (name "/EQ_Gain_6") (class "Default")
      (node (ref "U9") (pin "13") (pinfunction "0_13") (pintype "passive"))
    )
    (net (code "42") (name "/EQ_Gain_7") (class "Default")
      (node (ref "U9") (pin "12") (pinfunction "3_12") (pintype "passive"))
    )
    (net (code "43") (name "/EQ_Gain_8") (class "Default")
      (node (ref "U9") (pin "2") (pinfunction "6_2") (pintype "passive"))
    )
    (net (code "44") (name "/Frequency_1") (class "Default")
      (node (ref "U5") (pin "13") (pinfunction "0_13") (pintype "passive"))
    )
    (net (code "45") (name "/Frequency_2") (class "Default")
      (node (ref "U5") (pin "12") (pinfunction "3_12") (pintype "passive"))
    )
    (net (code "46") (name "/Frequency_3") (class "Default")
      (node (ref "U5") (pin "2") (pinfunction "6_2") (pintype "passive"))
    )
    (net (code "47") (name "/Frequency_4") (class "Default")
      (node (ref "U8") (pin "14") (pinfunction "1_14") (pintype "passive"))
    )
    (net (code "48") (name "/Frequency_5") (class "Default")
      (node (ref "U8") (pin "1") (pinfunction "4_1") (pintype "passive"))
    )
    (net (code "49") (name "/Frequency_6") (class "Default")
      (node (ref "U8") (pin "4") (pinfunction "7_4") (pintype "passive"))
    )
    (net (code "50") (name "/Frequency_7") (class "Default")
      (node (ref "U9") (pin "15") (pinfunction "2_15") (pintype "passive"))
    )
    (net (code "51") (name "/Frequency_8") (class "Default")
      (node (ref "U9") (pin "5") (pinfunction "5_5") (pintype "passive"))
    )
    (net (code "52") (name "/GEN_BTN_1") (class "Default")
      (node (ref "C5") (pin "1") (pinfunction "Anode_1") (pintype "passive"))
      (node (ref "R7") (pin "2") (pinfunction "2_2") (pintype "passive"))
      (node (ref "SW2") (pin "1") (pinfunction "1_1") (pintype "passive"))
      (node (ref "U2") (pin "1") (pinfunction "P00_1") (pintype "passive"))
    )
    (net (code "53") (name "/GEN_BTN_2") (class "Default")
      (node (ref "C7") (pin "1") (pinfunction "Anode_1") (pintype "passive"))
      (node (ref "R13") (pin "2") (pinfunction "2_2") (pintype "passive"))
      (node (ref "SW4") (pin "1") (pinfunction "1_1") (pintype "passive"))
      (node (ref "U2") (pin "2") (pinfunction "P01_2") (pintype "passive"))
    )
    (net (code "54") (name "/GEN_BTN_3") (class "Default")
      (node (ref "C9") (pin "1") (pinfunction "Anode_1") (pintype "passive"))
      (node (ref "R23") (pin "2") (pinfunction "2_2") (pintype "passive"))
      (node (ref "SW6") (pin "1") (pinfunction "1_1") (pintype "passive"))
      (node (ref "U2") (pin "3") (pinfunction "P02_3") (pintype "passive"))
    )
    (net (code "55") (name "/GEN_BTN_4") (class "Default")
      (node (ref "C11") (pin "1") (pinfunction "Anode_1") (pintype "passive"))
      (node (ref "R27") (pin "2") (pinfunction "2_2") (pintype "passive"))
      (node (ref "SW8") (pin "1") (pinfunction "1_1") (pintype "passive"))
      (node (ref "U2") (pin "4") (pinfunction "P03_4") (pintype "passive"))
    )
    (net (code "56") (name "/GEN_BTN_5") (class "Default")
      (node (ref "C6") (pin "1") (pinfunction "Anode_1") (pintype "passive"))
      (node (ref "R8") (pin "2") (pinfunction "2_2") (pintype "passive"))
      (node (ref "SW3") (pin "1") (pinfunction "1_1") (pintype "passive"))
      (node (ref "U2") (pin "5") (pinfunction "P04_5") (pintype "passive"))
    )
    (net (code "57") (name "/GEN_BTN_6") (class "Default")
      (node (ref "C8") (pin "1") (pinfunction "Anode_1") (pintype "passive"))
      (node (ref "R14") (pin "2") (pinfunction "2_2") (pintype "passive"))
      (node (ref "SW5") (pin "1") (pinfunction "1_1") (pintype "passive"))
      (node (ref "U2") (pin "6") (pinfunction "P05_6") (pintype "passive"))
    )
    (net (code "58") (name "/GEN_BTN_7") (class "Default")
      (node (ref "C10") (pin "1") (pinfunction "Anode_1") (pintype "passive"))
      (node (ref "R24") (pin "2") (pinfunction "2_2") (pintype "passive"))
      (node (ref "SW7") (pin "1") (pinfunction "1_1") (pintype "passive"))
      (node (ref "U2") (pin "7") (pinfunction "P06_7") (pintype "passive"))
    )
    (net (code "59") (name "/GEN_BTN_8") (class "Default")
      (node (ref "C12") (pin "1") (pinfunction "Anode_1") (pintype "passive"))
      (node (ref "R28") (pin "2") (pinfunction "2_2") (pintype "passive"))
      (node (ref "SW9") (pin "1") (pinfunction "1_1") (pintype "passive"))
      (node (ref "U2") (pin "8") (pinfunction "P07_8") (pintype "passive"))
    )
    (net (code "60") (name "/GEN_KNOB_1") (class "Default")
      (node (ref "R43") (pin "2") (pinfunction "2_2") (pintype "passive"))
      (node (ref "U3") (pin "13") (pinfunction "0_13") (pintype "passive"))
    )
    (net (code "61") (name "/GEN_KNOB_2") (class "Default")
      (node (ref "R49") (pin "2") (pinfunction "2_2") (pintype "passive"))
      (node (ref "U3") (pin "14") (pinfunction "1_14") (pintype "passive"))
    )
    (net (code "62") (name "/GEN_KNOB_3") (class "Default")
      (node (ref "R53") (pin "2") (pinfunction "2_2") (pintype "passive"))
      (node (ref "U3") (pin "15") (pinfunction "2_15") (pintype "passive"))
    )
    (net (code "63") (name "/GEN_KNOB_4") (class "Default")
      (node (ref "R57") (pin "2") (pinfunction "2_2") (pintype "passive"))
      (node (ref "U3") (pin "12") (pinfunction "3_12") (pintype "passive"))
    )
    (net (code "64") (name "/GEN_KNOB_5") (class "Default")
      (node (ref "R44") (pin "2") (pinfunction "2_2") (pintype "passive"))
      (node (ref "U3") (pin "1") (pinfunction "4_1") (pintype "passive"))
    )
    (net (code "65") (name "/GEN_KNOB_6") (class "Default")
      (node (ref "R50") (pin "2") (pinfunction "2_2") (pintype "passive"))
      (node (ref "U3") (pin "5") (pinfunction "5_5") (pintype "passive"))
    )
    (net (code "66") (name "/GEN_KNOB_7") (class "Default")
      (node (ref "R54") (pin "2") (pinfunction "2_2") (pintype "passive"))
      (node (ref "U3") (pin "2") (pinfunction "6_2") (pintype "passive"))
    )
    (net (code "67") (name "/GEN_KNOB_8") (class "Default")
      (node (ref "R58") (pin "2") (pinfunction "2_2") (pintype "passive"))
      (node (ref "U3") (pin "4") (pinfunction "7_4") (pintype "passive"))
    )
    (net (code "68") (name "/GEN_LED_1") (class "Default")
      (node (ref "LED2") (pin "1") (pinfunction "1_1") (pintype "passive"))
      (node (ref "U2") (pin "9") (pinfunction "P10_9") (pintype "passive"))
    )
    (net (code "69") (name "/GEN_LED_2") (class "Default")
      (node (ref "LED4") (pin "1") (pinfunction "1_1") (pintype "passive"))
      (node (ref "U2") (pin "10") (pinfunction "P11_10") (pintype "passive"))
    )
    (net (code "70") (name "/GEN_LED_3") (class "Default")
      (node (ref "LED6") (pin "1") (pinfunction "1_1") (pintype "passive"))
      (node (ref "U2") (pin "11") (pinfunction "P12_11") (pintype "passive"))
    )
    (net (code "71") (name "/GEN_LED_4") (class "Default")
      (node (ref "LED8") (pin "1") (pinfunction "1_1") (pintype "passive"))
      (node (ref "U2") (pin "12") (pinfunction "P13_12") (pintype "passive"))
    )
    (net (code "72") (name "/GEN_LED_5") (class "Default")
      (node (ref "LED3") (pin "1") (pinfunction "1_1") (pintype "passive"))
      (node (ref "U2") (pin "13") (pinfunction "P14_13") (pintype "passive"))
    )
    (net (code "73") (name "/GEN_LED_6") (class "Default")
      (node (ref "LED5") (pin "1") (pinfunction "1_1") (pintype "passive"))
      (node (ref "U2") (pin "14") (pinfunction "P15_14") (pintype "passive"))
    )
    (net (code "74") (name "/GEN_LED_7") (class "Default")
      (node (ref "LED7") (pin "1") (pinfunction "1_1") (pintype "passive"))
      (node (ref "U2") (pin "15") (pinfunction "P16_15") (pintype "passive"))
    )
    (net (code "75") (name "/GEN_LED_8") (class "Default")
      (node (ref "LED9") (pin "1") (pinfunction "1_1") (pintype "passive"))
      (node (ref "U2") (pin "16") (pinfunction "P17_16") (pintype "passive"))
    )
    (net (code "76") (name "/Gain_1") (class "Default")
      (node (ref "U5") (pin "15") (pinfunction "2_15") (pintype "passive"))
    )
    (net (code "77") (name "/Gain_2") (class "Default")
      (node (ref "U5") (pin "5") (pinfunction "5_5") (pintype "passive"))
    )
    (net (code "78") (name "/Gain_3") (class "Default")
      (node (ref "U8") (pin "13") (pinfunction "0_13") (pintype "passive"))
    )
    (net (code "79") (name "/Gain_4") (class "Default")
      (node (ref "U8") (pin "12") (pinfunction "3_12") (pintype "passive"))
    )
    (net (code "80") (name "/Gain_5") (class "Default")
      (node (ref "U8") (pin "2") (pinfunction "6_2") (pintype "passive"))
    )
    (net (code "81") (name "/Gain_6") (class "Default")
      (node (ref "U9") (pin "14") (pinfunction "1_14") (pintype "passive"))
    )
    (net (code "82") (name "/Gain_7") (class "Default")
      (node (ref "U9") (pin "1") (pinfunction "4_1") (pintype "passive"))
    )
    (net (code "83") (name "/Gain_8") (class "Default")
      (node (ref "U9") (pin "4") (pinfunction "7_4") (pintype "passive"))
    )
    (net (code "84") (name "/INH_0") (class "Default")
      (node (ref "U5") (pin "6") (pinfunction "INH_6") (pintype "input"))
      (node (ref "U6") (pin "4") (pinfunction "~{Q0}_4") (pintype "output"))
    )
    (net (code "85") (name "/INH_1") (class "Default")
      (node (ref "U6") (pin "5") (pinfunction "~{Q1}_5") (pintype "output"))
      (node (ref "U8") (pin "6") (pinfunction "INH_6") (pintype "input"))
    )
    (net (code "86") (name "/INH_2") (class "Default")
      (node (ref "U6") (pin "6") (pinfunction "~{Q2}_6") (pintype "output"))
      (node (ref "U9") (pin "6") (pinfunction "INH_6") (pintype "input"))
    )
    (net (code "87") (name "/INT_1") (class "Default")
      (node (ref "R52") (pin "1") (pinfunction "1_1") (pintype "passive"))
      (node (ref "U4") (pin "41") (pinfunction "RB5_41") (pintype "input"))
      (node (ref "U7") (pin "32") (pinfunction "INTbar_32") (pintype "passive"))
    )
    (net (code "88") (name "/INT_2") (class "Default")
      (node (ref "R40") (pin "1") (pinfunction "1_1") (pintype "passive"))
      (node (ref "U2") (pin "32") (pinfunction "INTbar_32") (pintype "passive"))
      (node (ref "U4") (pin "42") (pinfunction "RB6_42") (pintype "input"))
    )
    (net (code "89") (name "/IO_1") (class "Default")
      (node (ref "HEADER1") (pin "1") (pinfunction "1_1") (pintype "passive"))
      (node (ref "U4") (pin "20") (pinfunction "RA1_20") (pintype "input"))
    )
    (net (code "90") (name "/IO_2") (class "Default")
      (node (ref "HEADER1") (pin "2") (pinfunction "2_2") (pintype "passive"))
      (node (ref "U4") (pin "30") (pinfunction "RA2_30") (pintype "input"))
    )
    (net (code "91") (name "/IO_3") (class "Default")
      (node (ref "HEADER1") (pin "3") (pinfunction "3_3") (pintype "passive"))
      (node (ref "U4") (pin "31") (pinfunction "RA3_31") (pintype "input"))
    )
    (net (code "92") (name "/IO_4") (class "Default")
      (node (ref "HEADER1") (pin "4") (pinfunction "4_4") (pintype "passive"))
      (node (ref "U4") (pin "32") (pinfunction "RA8_32") (pintype "input"))
    )
    (net (code "93") (name "/IO_5") (class "Default")
      (node (ref "HEADER1") (pin "5") (pinfunction "5_5") (pintype "passive"))
      (node (ref "U4") (pin "33") (pinfunction "RB4_33") (pintype "input"))
    )
    (net (code "94") (name "/IO_6") (class "Default")
      (node (ref "HEADER1") (pin "6") (pinfunction "6_6") (pintype "passive"))
      (node (ref "U4") (pin "34") (pinfunction "RA4_34") (pintype "input"))
    )
    (net (code "95") (name "/MCLRbar") (class "Default")
      (node (ref "C30") (pin "1") (pinfunction "Anode_1") (pintype "passive"))
      (node (ref "P2") (pin "1") (pinfunction "1_1") (pintype "passive"))
      (node (ref "R51") (pin "2") (pinfunction "2_2") (pintype "passive"))
      (node (ref "R56") (pin "1") (pinfunction "1_1") (pintype "passive"))
      (node (ref "SW10") (pin "1") (pinfunction "1_1") (pintype "passive"))
    )
    (net (code "96") (name "/MCU_RX") (class "Default")
      (node (ref "U4") (pin "43") (pinfunction "RB7_43") (pintype "input"))
    )
    (net (code "97") (name "/MCU_TX") (class "Default")
      (node (ref "U4") (pin "44") (pinfunction "RB8_44") (pintype "input"))
    )
    (net (code "98") (name "/Mute_1") (class "Default")
      (node (ref "U7") (pin "1") (pinfunction "P00_1") (pintype "passive"))
    )
    (net (code "99") (name "/Mute_2") (class "Default")
      (node (ref "U7") (pin "4") (pinfunction "P03_4") (pintype "passive"))
    )
    (net (code "100") (name "/Mute_3") (class "Default")
      (node (ref "U7") (pin "7") (pinfunction "P06_7") (pintype "passive"))
    )
    (net (code "101") (name "/Mute_4") (class "Default")
      (node (ref "U7") (pin "10") (pinfunction "P11_10") (pintype "passive"))
    )
    (net (code "102") (name "/Mute_5") (class "Default")
      (node (ref "U7") (pin "13") (pinfunction "P14_13") (pintype "passive"))
    )
    (net (code "103") (name "/Mute_6") (class "Default")
      (node (ref "U7") (pin "16") (pinfunction "P17_16") (pintype "passive"))
    )
    (net (code "104") (name "/Mute_7") (class "Default")
      (node (ref "U7") (pin "19") (pinfunction "P22_19") (pintype "passive"))
    )
    (net (code "105") (name "/Mute_8") (class "Default")
      (node (ref "U7") (pin "22") (pinfunction "P25_22") (pintype "passive"))
    )
    (net (code "106") (name "/PGC") (class "Default")
      (node (ref "P2") (pin "9") (pinfunction "9_9") (pintype "passive"))
      (node (ref "U4") (pin "22") (pinfunction "RB1_22") (pintype "input"))
    )
    (net (code "107") (name "/PGD") (class "Default")
      (node (ref "P2") (pin "7") (pinfunction "7_7") (pintype "passive"))
      (node (ref "U4") (pin "21") (pinfunction "RB0_21") (pintype "input"))
    )
    (net (code "108") (name "/RST 1") (class "Default")
      (node (ref "R55") (pin "1") (pinfunction "1_1") (pintype "passive"))
      (node (ref "U7") (pin "28") (pinfunction "RESETbar_28") (pintype "passive"))
    )
    (net (code "109") (name "/RST 2") (class "Default")
      (node (ref "R41") (pin "1") (pinfunction "1_1") (pintype "passive"))
      (node (ref "U2") (pin "28") (pinfunction "RESETbar_28") (pintype "passive"))
    )
    (net (code "110") (name "/SCL") (class "Default")
      (node (ref "R48") (pin "1") (pinfunction "1_1") (pintype "passive"))
      (node (ref "U2") (pin "29") (pinfunction "SCL_29") (pintype "passive"))
      (node (ref "U4") (pin "23") (pinfunction "RB2_23") (pintype "input"))
      (node (ref "U7") (pin "29") (pinfunction "SCL_29") (pintype "passive"))
    )
    (net (code "111") (name "/SDA") (class "Default")
      (node (ref "R46") (pin "1") (pinfunction "1_1") (pintype "passive"))
      (node (ref "U2") (pin "30") (pinfunction "SDA_30") (pintype "passive"))
      (node (ref "U4") (pin "24") (pinfunction "RB3_24") (pintype "input"))
      (node (ref "U7") (pin "30") (pinfunction "SDA_30") (pintype "passive"))
    )
    (net (code "112") (name "/Select_1") (class "Default")
      (node (ref "U7") (pin "3") (pinfunction "P02_3") (pintype "passive"))
    )
    (net (code "113") (name "/Select_2") (class "Default")
      (node (ref "U7") (pin "6") (pinfunction "P05_6") (pintype "passive"))
    )
    (net (code "114") (name "/Select_3") (class "Default")
      (node (ref "U7") (pin "9") (pinfunction "P10_9") (pintype "passive"))
    )
    (net (code "115") (name "/Select_4") (class "Default")
      (node (ref "U7") (pin "12") (pinfunction "P13_12") (pintype "passive"))
    )
    (net (code "116") (name "/Select_5") (class "Default")
      (node (ref "U7") (pin "15") (pinfunction "P16_15") (pintype "passive"))
    )
    (net (code "117") (name "/Select_6") (class "Default")
      (node (ref "U7") (pin "18") (pinfunction "P21_18") (pintype "passive"))
    )
    (net (code "118") (name "/Select_7") (class "Default")
      (node (ref "U7") (pin "21") (pinfunction "P24_21") (pintype "passive"))
    )
    (net (code "119") (name "/Select_8") (class "Default")
      (node (ref "U7") (pin "24") (pinfunction "P27_24") (pintype "passive"))
    )
    (net (code "120") (name "/Solo_1") (class "Default")
      (node (ref "U7") (pin "2") (pinfunction "P01_2") (pintype "passive"))
    )
    (net (code "121") (name "/Solo_2") (class "Default")
      (node (ref "U7") (pin "5") (pinfunction "P04_5") (pintype "passive"))
    )
    (net (code "122") (name "/Solo_3") (class "Default")
      (node (ref "U7") (pin "8") (pinfunction "P07_8") (pintype "passive"))
    )
    (net (code "123") (name "/Solo_4") (class "Default")
      (node (ref "U7") (pin "11") (pinfunction "P12_11") (pintype "passive"))
    )
    (net (code "124") (name "/Solo_5") (class "Default")
      (node (ref "U7") (pin "14") (pinfunction "P15_14") (pintype "passive"))
    )
    (net (code "125") (name "/Solo_6") (class "Default")
      (node (ref "U7") (pin "17") (pinfunction "P20_17") (pintype "passive"))
    )
    (net (code "126") (name "/Solo_7") (class "Default")
      (node (ref "U7") (pin "20") (pinfunction "P23_20") (pintype "passive"))
    )
    (net (code "127") (name "/Solo_8") (class "Default")
      (node (ref "U7") (pin "23") (pinfunction "P26_23") (pintype "passive"))
    )
    (net (code "134") (name "3V3") (class "Default")
      (node (ref "C13") (pin "1") (pinfunction "Anode_1") (pintype "passive"))
      (node (ref "C14") (pin "1") (pinfunction "Anode_1") (pintype "passive"))
      (node (ref "C15") (pin "1") (pinfunction "Anode_1") (pintype "passive"))
      (node (ref "C16") (pin "1") (pinfunction "Anode_1") (pintype "passive"))
      (node (ref "C17") (pin "1") (pinfunction "Anode_1") (pintype "passive"))
      (node (ref "C18") (pin "1") (pinfunction "Anode_1") (pintype "passive"))
      (node (ref "C19") (pin "1") (pinfunction "Anode_1") (pintype "passive"))
      (node (ref "C20") (pin "1") (pinfunction "Anode_1") (pintype "passive"))
      (node (ref "C21") (pin "1") (pinfunction "Anode_1") (pintype "passive"))
      (node (ref "C22") (pin "1") (pinfunction "Anode_1") (pintype "passive"))
      (node (ref "C23") (pin "1") (pinfunction "Anode_1") (pintype "passive"))
      (node (ref "C25") (pin "1") (pinfunction "Anode_1") (pintype "passive"))
      (node (ref "C26") (pin "1") (pinfunction "Anode_1") (pintype "passive"))
      (node (ref "C27") (pin "1") (pinfunction "Anode_1") (pintype "passive"))
      (node (ref "C28") (pin "1") (pinfunction "Anode_1") (pintype "passive"))
      (node (ref "C29") (pin "1") (pinfunction "Anode_1") (pintype "passive"))
      (node (ref "C31") (pin "1") (pinfunction "Anode_1") (pintype "passive"))
      (node (ref "C32") (pin "1") (pinfunction "Anode_1") (pintype "passive"))
      (node (ref "C33") (pin "1") (pinfunction "Anode_1") (pintype "passive"))
      (node (ref "C34") (pin "1") (pinfunction "Anode_1") (pintype "passive"))
      (node (ref "C35") (pin "1") (pinfunction "Anode_1") (pintype "passive"))
      (node (ref "C36") (pin "1") (pinfunction "Anode_1") (pintype "passive"))
      (node (ref "C37") (pin "1") (pinfunction "Anode_1") (pintype "passive"))
      (node (ref "HEADER2") (pin "1") (pinfunction "1_1") (pintype "passive"))
      (node (ref "HEADER2") (pin "3") (pinfunction "3_3") (pintype "passive"))
      (node (ref "HEADER2") (pin "5") (pinfunction "5_5") (pintype "passive"))
      (node (ref "HEADER2") (pin "7") (pinfunction "7_7") (pintype "passive"))
      (node (ref "HEADER2") (pin "9") (pinfunction "9_9") (pintype "passive"))
      (node (ref "P2") (pin "3") (pinfunction "3_3") (pintype "passive"))
      (node (ref "R13") (pin "1") (pinfunction "1_1") (pintype "passive"))
      (node (ref "R14") (pin "1") (pinfunction "1_1") (pintype "passive"))
      (node (ref "R15") (pin "2") (pinfunction "2_2") (pintype "passive"))
      (node (ref "R16") (pin "2") (pinfunction "2_2") (pintype "passive"))
      (node (ref "R17") (pin "2") (pinfunction "2_2") (pintype "passive"))
      (node (ref "R18") (pin "2") (pinfunction "2_2") (pintype "passive"))
      (node (ref "R23") (pin "1") (pinfunction "1_1") (pintype "passive"))
      (node (ref "R24") (pin "1") (pinfunction "1_1") (pintype "passive"))
      (node (ref "R25") (pin "1") (pinfunction "1_1") (pintype "passive"))
      (node (ref "R26") (pin "1") (pinfunction "1_1") (pintype "passive"))
      (node (ref "R27") (pin "1") (pinfunction "1_1") (pintype "passive"))
      (node (ref "R28") (pin "1") (pinfunction "1_1") (pintype "passive"))
      (node (ref "R29") (pin "1") (pinfunction "1_1") (pintype "passive"))
      (node (ref "R3") (pin "2") (pinfunction "2_2") (pintype "passive"))
      (node (ref "R30") (pin "1") (pinfunction "1_1") (pintype "passive"))
      (node (ref "R31") (pin "1") (pinfunction "1_1") (pintype "passive"))
      (node (ref "R32") (pin "1") (pinfunction "1_1") (pintype "passive"))
      (node (ref "R33") (pin "1") (pinfunction "1_1") (pintype "passive"))
      (node (ref "R34") (pin "1") (pinfunction "1_1") (pintype "passive"))
      (node (ref "R35") (pin "2") (pinfunction "2_2") (pintype "passive"))
      (node (ref "R38") (pin "2") (pinfunction "2_2") (pintype "passive"))
      (node (ref "R4") (pin "2") (pinfunction "2_2") (pintype "passive"))
      (node (ref "R40") (pin "2") (pinfunction "2_2") (pintype "passive"))
      (node (ref "R41") (pin "2") (pinfunction "2_2") (pintype "passive"))
      (node (ref "R43") (pin "1") (pinfunction "1_1") (pintype "passive"))
      (node (ref "R44") (pin "1") (pinfunction "1_1") (pintype "passive"))
      (node (ref "R45") (pin "2") (pinfunction "2_2") (pintype "passive"))
      (node (ref "R46") (pin "2") (pinfunction "2_2") (pintype "passive"))
      (node (ref "R48") (pin "2") (pinfunction "2_2") (pintype "passive"))
      (node (ref "R49") (pin "1") (pinfunction "1_1") (pintype "passive"))
      (node (ref "R5") (pin "2") (pinfunction "2_2") (pintype "passive"))
      (node (ref "R50") (pin "1") (pinfunction "1_1") (pintype "passive"))
      (node (ref "R51") (pin "1") (pinfunction "1_1") (pintype "passive"))
      (node (ref "R52") (pin "2") (pinfunction "2_2") (pintype "passive"))
      (node (ref "R53") (pin "1") (pinfunction "1_1") (pintype "passive"))
      (node (ref "R54") (pin "1") (pinfunction "1_1") (pintype "passive"))
      (node (ref "R55") (pin "2") (pinfunction "2_2") (pintype "passive"))
      (node (ref "R57") (pin "1") (pinfunction "1_1") (pintype "passive"))
      (node (ref "R58") (pin "1") (pinfunction "1_1") (pintype "passive"))
      (node (ref "R6") (pin "2") (pinfunction "2_2") (pintype "passive"))
      (node (ref "R7") (pin "1") (pinfunction "1_1") (pintype "passive"))
      (node (ref "R8") (pin "1") (pinfunction "1_1") (pintype "passive"))
      (node (ref "U2") (pin "27") (pinfunction "VCCP_27") (pintype "passive"))
      (node (ref "U2") (pin "31") (pinfunction "VCCI_31") (pintype "passive"))
      (node (ref "U3") (pin "16") (pinfunction "VDD_16") (pintype "power_in"))
      (node (ref "U4") (pin "17") (pinfunction "AVDD_17") (pintype "input"))
      (node (ref "U4") (pin "28") (pinfunction "VDD_28") (pintype "input"))
      (node (ref "U4") (pin "40") (pinfunction "VDD_40") (pintype "input"))
      (node (ref "U4") (pin "6") (pinfunction "VBAT_6") (pintype "input"))
      (node (ref "U5") (pin "16") (pinfunction "VDD_16") (pintype "power_in"))
      (node (ref "U6") (pin "16") (pinfunction "VDD_16") (pintype "power_in"))
      (node (ref "U7") (pin "27") (pinfunction "VCCP_27") (pintype "passive"))
      (node (ref "U7") (pin "31") (pinfunction "VCCI_31") (pintype "passive"))
      (node (ref "U8") (pin "16") (pinfunction "VDD_16") (pintype "power_in"))
      (node (ref "U9") (pin "16") (pinfunction "VDD_16") (pintype "power_in"))
    )
    (net (code "135") (name "DGND") (class "Default")
      (node (ref "C10") (pin "2") (pinfunction "Cathode_2") (pintype "passive"))
      (node (ref "C11") (pin "2") (pinfunction "Cathode_2") (pintype "passive"))
      (node (ref "C12") (pin "2") (pinfunction "Cathode_2") (pintype "passive"))
      (node (ref "C13") (pin "2") (pinfunction "Cathode_2") (pintype "passive"))
      (node (ref "C14") (pin "2") (pinfunction "Cathode_2") (pintype "passive"))
      (node (ref "C15") (pin "2") (pinfunction "Cathode_2") (pintype "passive"))
      (node (ref "C16") (pin "2") (pinfunction "Cathode_2") (pintype "passive"))
      (node (ref "C17") (pin "2") (pinfunction "Cathode_2") (pintype "passive"))
      (node (ref "C18") (pin "2") (pinfunction "Cathode_2") (pintype "passive"))
      (node (ref "C19") (pin "2") (pinfunction "Cathode_2") (pintype "passive"))
      (node (ref "C20") (pin "2") (pinfunction "Cathode_2") (pintype "passive"))
      (node (ref "C21") (pin "2") (pinfunction "Cathode_2") (pintype "passive"))
      (node (ref "C22") (pin "2") (pinfunction "Cathode_2") (pintype "passive"))
      (node (ref "C23") (pin "2") (pinfunction "Cathode_2") (pintype "passive"))
      (node (ref "C24") (pin "2") (pinfunction "Cathode_2") (pintype "passive"))
      (node (ref "C25") (pin "2") (pinfunction "Cathode_2") (pintype "passive"))
      (node (ref "C26") (pin "2") (pinfunction "Cathode_2") (pintype "passive"))
      (node (ref "C27") (pin "2") (pinfunction "Cathode_2") (pintype "passive"))
      (node (ref "C28") (pin "2") (pinfunction "Cathode_2") (pintype "passive"))
      (node (ref "C29") (pin "2") (pinfunction "Cathode_2") (pintype "passive"))
      (node (ref "C30") (pin "2") (pinfunction "Cathode_2") (pintype "passive"))
      (node (ref "C31") (pin "2") (pinfunction "Cathode_2") (pintype "passive"))
      (node (ref "C32") (pin "2") (pinfunction "Cathode_2") (pintype "passive"))
      (node (ref "C33") (pin "2") (pinfunction "Cathode_2") (pintype "passive"))
      (node (ref "C34") (pin "2") (pinfunction "Cathode_2") (pintype "passive"))
      (node (ref "C35") (pin "2") (pinfunction "Cathode_2") (pintype "passive"))
      (node (ref "C36") (pin "2") (pinfunction "Cathode_2") (pintype "passive"))
      (node (ref "C37") (pin "2") (pinfunction "Cathode_2") (pintype "passive"))
      (node (ref "C45") (pin "2") (pinfunction "Cathode_2") (pintype "passive"))
      (node (ref "C46") (pin "2") (pinfunction "Cathode_2") (pintype "passive"))
      (node (ref "C5") (pin "2") (pinfunction "Cathode_2") (pintype "passive"))
      (node (ref "C6") (pin "2") (pinfunction "Cathode_2") (pintype "passive"))
      (node (ref "C7") (pin "2") (pinfunction "Cathode_2") (pintype "passive"))
      (node (ref "C8") (pin "2") (pinfunction "Cathode_2") (pintype "passive"))
      (node (ref "C9") (pin "2") (pinfunction "Cathode_2") (pintype "passive"))
      (node (ref "HEADER2") (pin "10") (pinfunction "10_10") (pintype "passive"))
      (node (ref "HEADER2") (pin "2") (pinfunction "2_2") (pintype "passive"))
      (node (ref "HEADER2") (pin "4") (pinfunction "4_4") (pintype "passive"))
      (node (ref "HEADER2") (pin "6") (pinfunction "6_6") (pintype "passive"))
      (node (ref "HEADER2") (pin "8") (pinfunction "8_8") (pintype "passive"))
      (node (ref "LED10") (pin "1") (pinfunction "1_1") (pintype "passive"))
      (node (ref "P2") (pin "5") (pinfunction "5_5") (pintype "passive"))
      (node (ref "R10") (pin "1") (pinfunction "1_1") (pintype "passive"))
      (node (ref "R11") (pin "1") (pinfunction "1_1") (pintype "passive"))
      (node (ref "R12") (pin "1") (pinfunction "1_1") (pintype "passive"))
      (node (ref "R19") (pin "1") (pinfunction "1_1") (pintype "passive"))
      (node (ref "R20") (pin "1") (pinfunction "1_1") (pintype "passive"))
      (node (ref "R21") (pin "1") (pinfunction "1_1") (pintype "passive"))
      (node (ref "R22") (pin "1") (pinfunction "1_1") (pintype "passive"))
      (node (ref "R37") (pin "1") (pinfunction "1_1") (pintype "passive"))
      (node (ref "R39") (pin "1") (pinfunction "1_1") (pintype "passive"))
      (node (ref "R43") (pin "3") (pinfunction "3_3") (pintype "passive"))
      (node (ref "R44") (pin "3") (pinfunction "3_3") (pintype "passive"))
      (node (ref "R47") (pin "1") (pinfunction "1_1") (pintype "passive"))
      (node (ref "R49") (pin "3") (pinfunction "3_3") (pintype "passive"))
      (node (ref "R50") (pin "3") (pinfunction "3_3") (pintype "passive"))
      (node (ref "R53") (pin "3") (pinfunction "3_3") (pintype "passive"))
      (node (ref "R54") (pin "3") (pinfunction "3_3") (pintype "passive"))
      (node (ref "R57") (pin "3") (pinfunction "3_3") (pintype "passive"))
      (node (ref "R58") (pin "3") (pinfunction "3_3") (pintype "passive"))
      (node (ref "R9") (pin "1") (pinfunction "1_1") (pintype "passive"))
      (node (ref "SW10") (pin "2") (pinfunction "2_2") (pintype "passive"))
      (node (ref "SW2") (pin "2") (pinfunction "2_2") (pintype "passive"))
      (node (ref "SW3") (pin "2") (pinfunction "2_2") (pintype "passive"))
      (node (ref "SW4") (pin "2") (pinfunction "2_2") (pintype "passive"))
      (node (ref "SW5") (pin "2") (pinfunction "2_2") (pintype "passive"))
      (node (ref "SW6") (pin "2") (pinfunction "2_2") (pintype "passive"))
      (node (ref "SW7") (pin "2") (pinfunction "2_2") (pintype "passive"))
      (node (ref "SW8") (pin "2") (pinfunction "2_2") (pintype "passive"))
      (node (ref "SW9") (pin "2") (pinfunction "2_2") (pintype "passive"))
      (node (ref "U2") (pin "25") (pinfunction "GND_25") (pintype "passive"))
      (node (ref "U2") (pin "33") (pinfunction "EP_33") (pintype "passive"))
      (node (ref "U3") (pin "7") (pinfunction "VEE_7") (pintype "power_in"))
      (node (ref "U3") (pin "8") (pinfunction "VSS_8") (pintype "power_in"))
      (node (ref "U4") (pin "16") (pinfunction "AVSS/VSS_16") (pintype "input"))
      (node (ref "U4") (pin "29") (pinfunction "VSS_29") (pintype "input"))
      (node (ref "U4") (pin "39") (pinfunction "VSS_39") (pintype "input"))
      (node (ref "U5") (pin "7") (pinfunction "VEE_7") (pintype "power_in"))
      (node (ref "U5") (pin "8") (pinfunction "VSS_8") (pintype "power_in"))
      (node (ref "U6") (pin "1") (pinfunction "~{E}_1") (pintype "input"))
      (node (ref "U6") (pin "8") (pinfunction "VSS_8") (pintype "power_in"))
      (node (ref "U7") (pin "25") (pinfunction "GND_25") (pintype "passive"))
      (node (ref "U7") (pin "33") (pinfunction "EP_33") (pintype "passive"))
      (node (ref "U8") (pin "7") (pinfunction "VEE_7") (pintype "power_in"))
      (node (ref "U8") (pin "8") (pinfunction "VSS_8") (pintype "power_in"))
      (node (ref "U9") (pin "7") (pinfunction "VEE_7") (pintype "power_in"))
      (node (ref "U9") (pin "8") (pinfunction "VSS_8") (pintype "power_in"))
    )
    (net (code "136") (name "Net-(C24-Anode)") (class "Default")
      (node (ref "C24") (pin "1") (pinfunction "Anode_1") (pintype "passive"))
      (node (ref "U4") (pin "7") (pinfunction "VCAP_7") (pintype "input"))
    )
    (net (code "137") (name "Net-(C45-Anode)") (class "Default")
      (node (ref "C45") (pin "1") (pinfunction "Anode_1") (pintype "passive"))
      (node (ref "R72") (pin "1") (pinfunction "1_1") (pintype "passive"))
      (node (ref "U4") (pin "14") (pinfunction "RB14_14") (pintype "input"))
    )
    (net (code "138") (name "Net-(C46-Anode)") (class "Default")
      (node (ref "C46") (pin "1") (pinfunction "Anode_1") (pintype "passive"))
      (node (ref "R74") (pin "1") (pinfunction "1_1") (pintype "passive"))
      (node (ref "U4") (pin "15") (pinfunction "RB15_15") (pintype "input"))
    )
    (net (code "139") (name "Net-(LED2-Pad2)") (class "Default")
      (node (ref "LED2") (pin "2") (pinfunction "2_2") (pintype "passive"))
      (node (ref "R25") (pin "2") (pinfunction "2_2") (pintype "passive"))
    )
    (net (code "140") (name "Net-(LED3-Pad2)") (class "Default")
      (node (ref "LED3") (pin "2") (pinfunction "2_2") (pintype "passive"))
      (node (ref "R26") (pin "2") (pinfunction "2_2") (pintype "passive"))
    )
    (net (code "141") (name "Net-(LED4-Pad2)") (class "Default")
      (node (ref "LED4") (pin "2") (pinfunction "2_2") (pintype "passive"))
      (node (ref "R29") (pin "2") (pinfunction "2_2") (pintype "passive"))
    )
    (net (code "142") (name "Net-(LED5-Pad2)") (class "Default")
      (node (ref "LED5") (pin "2") (pinfunction "2_2") (pintype "passive"))
      (node (ref "R30") (pin "2") (pinfunction "2_2") (pintype "passive"))
    )
    (net (code "143") (name "Net-(LED6-Pad2)") (class "Default")
      (node (ref "LED6") (pin "2") (pinfunction "2_2") (pintype "passive"))
      (node (ref "R31") (pin "2") (pinfunction "2_2") (pintype "passive"))
    )
    (net (code "144") (name "Net-(LED7-Pad2)") (class "Default")
      (node (ref "LED7") (pin "2") (pinfunction "2_2") (pintype "passive"))
      (node (ref "R32") (pin "2") (pinfunction "2_2") (pintype "passive"))
    )
    (net (code "145") (name "Net-(LED8-Pad2)") (class "Default")
      (node (ref "LED8") (pin "2") (pinfunction "2_2") (pintype "passive"))
      (node (ref "R33") (pin "2") (pinfunction "2_2") (pintype "passive"))
    )
    (net (code "146") (name "Net-(LED9-Pad2)") (class "Default")
      (node (ref "LED9") (pin "2") (pinfunction "2_2") (pintype "passive"))
      (node (ref "R34") (pin "2") (pinfunction "2_2") (pintype "passive"))
    )
    (net (code "147") (name "Net-(LED10-Pad2)") (class "Default")
      (node (ref "LED10") (pin "2") (pinfunction "2_2") (pintype "passive"))
      (node (ref "R42") (pin "2") (pinfunction "2_2") (pintype "passive"))
    )
    (net (code "148") (name "Net-(U2-ADDR)") (class "Default")
      (node (ref "R35") (pin "1") (pinfunction "1_1") (pintype "passive"))
      (node (ref "R37") (pin "2") (pinfunction "2_2") (pintype "passive"))
      (node (ref "U2") (pin "26") (pinfunction "ADDR_26") (pintype "passive"))
    )
    (net (code "149") (name "Net-(U3-INH)") (class "Default")
      (node (ref "R38") (pin "1") (pinfunction "1_1") (pintype "passive"))
      (node (ref "R39") (pin "2") (pinfunction "2_2") (pintype "passive"))
      (node (ref "U3") (pin "6") (pinfunction "INH_6") (pintype "input"))
    )
    (net (code "150") (name "Net-(U4-MCLR')") (class "Default")
      (node (ref "R56") (pin "2") (pinfunction "2_2") (pintype "passive"))
      (node (ref "U4") (pin "18") (pinfunction "MCLR'_18") (pintype "input"))
    )
    (net (code "151") (name "Net-(U4-RA9)") (class "Default")
      (node (ref "R42") (pin "1") (pinfunction "1_1") (pintype "passive"))
      (node (ref "U4") (pin "35") (pinfunction "RA9_35") (pintype "input"))
    )
    (net (code "152") (name "Net-(U7-ADDR)") (class "Default")
      (node (ref "R45") (pin "1") (pinfunction "1_1") (pintype "passive"))
      (node (ref "R47") (pin "2") (pinfunction "2_2") (pintype "passive"))
      (node (ref "U7") (pin "26") (pinfunction "ADDR_26") (pintype "passive"))
    )
    (net (code "153") (name "unconnected-(HEADER1-Pad7)") (class "Default")
      (node (ref "HEADER1") (pin "7") (pinfunction "7_7") (pintype "passive"))
    )
    (net (code "154") (name "unconnected-(HEADER1-Pad8)") (class "Default")
      (node (ref "HEADER1") (pin "8") (pinfunction "8_8") (pintype "passive"))
    )
    (net (code "155") (name "unconnected-(HEADER1-Pad9)") (class "Default")
      (node (ref "HEADER1") (pin "9") (pinfunction "9_9") (pintype "passive"))
    )
    (net (code "156") (name "unconnected-(HEADER1-Pad10)") (class "Default")
      (node (ref "HEADER1") (pin "10") (pinfunction "10_10") (pintype "passive"))
    )
    (net (code "157") (name "unconnected-(P2-Pad2)") (class "Default")
      (node (ref "P2") (pin "2") (pinfunction "2_2") (pintype "passive"))
    )
    (net (code "158") (name "unconnected-(P2-Pad4)") (class "Default")
      (node (ref "P2") (pin "4") (pinfunction "4_4") (pintype "passive"))
    )
    (net (code "159") (name "unconnected-(P2-Pad6)") (class "Default")
      (node (ref "P2") (pin "6") (pinfunction "6_6") (pintype "passive"))
    )
    (net (code "160") (name "unconnected-(P2-Pad8)") (class "Default")
      (node (ref "P2") (pin "8") (pinfunction "8_8") (pintype "passive"))
    )
    (net (code "161") (name "unconnected-(P2-Pad10)") (class "Default")
      (node (ref "P2") (pin "10") (pinfunction "10_10") (pintype "passive"))
    )
    (net (code "162") (name "unconnected-(R36-Pad1)") (class "Default")
      (node (ref "R36") (pin "1") (pinfunction "1_1") (pintype "passive"))
    )
    (net (code "163") (name "unconnected-(R36-Pad2)") (class "Default")
      (node (ref "R36") (pin "2") (pinfunction "2_2") (pintype "passive"))
    )
    (net (code "164") (name "unconnected-(U4-BA10-Pad12)") (class "Default")
      (node (ref "U4") (pin "12") (pinfunction "BA10_12") (pintype "input+no_connect"))
    )
    (net (code "165") (name "unconnected-(U4-GB12-Pad10)") (class "Default")
      (node (ref "U4") (pin "10") (pinfunction "GB12_10") (pintype "input+no_connect"))
    )
    (net (code "166") (name "unconnected-(U4-RA0-Pad19)") (class "Default")
      (node (ref "U4") (pin "19") (pinfunction "RA0_19") (pintype "input+no_connect"))
    )
    (net (code "167") (name "unconnected-(U4-RA7-Pad13)") (class "Default")
      (node (ref "U4") (pin "13") (pinfunction "RA7_13") (pintype "input+no_connect"))
    )
    (net (code "168") (name "unconnected-(U4-RB9-Pad1)") (class "Default")
      (node (ref "U4") (pin "1") (pinfunction "RB9_1") (pintype "input+no_connect"))
    )
    (net (code "169") (name "unconnected-(U4-RB10-Pad8)") (class "Default")
      (node (ref "U4") (pin "8") (pinfunction "RB10_8") (pintype "input+no_connect"))
    )
    (net (code "170") (name "unconnected-(U4-RB11-Pad9)") (class "Default")
      (node (ref "U4") (pin "9") (pinfunction "RB11_9") (pintype "input+no_connect"))
    )
    (net (code "171") (name "unconnected-(U4-RB13-Pad11)") (class "Default")
      (node (ref "U4") (pin "11") (pinfunction "RB13_11") (pintype "input+no_connect"))
    )
    (net (code "172") (name "unconnected-(U4-RC8-Pad4)") (class "Default")
      (node (ref "U4") (pin "4") (pinfunction "RC8_4") (pintype "input+no_connect"))
    )
    (net (code "173") (name "unconnected-(U4-RC9-Pad5)") (class "Default")
      (node (ref "U4") (pin "5") (pinfunction "RC9_5") (pintype "input+no_connect"))
    )
    (net (code "174") (name "unconnected-(U6A-~{Q3}-Pad7)") (class "Default")
      (node (ref "U6") (pin "7") (pinfunction "~{Q3}_7") (pintype "output"))
    )
  )
)
